# SCH.net
KiCad netlist of a schematic drawn in Altium Designer
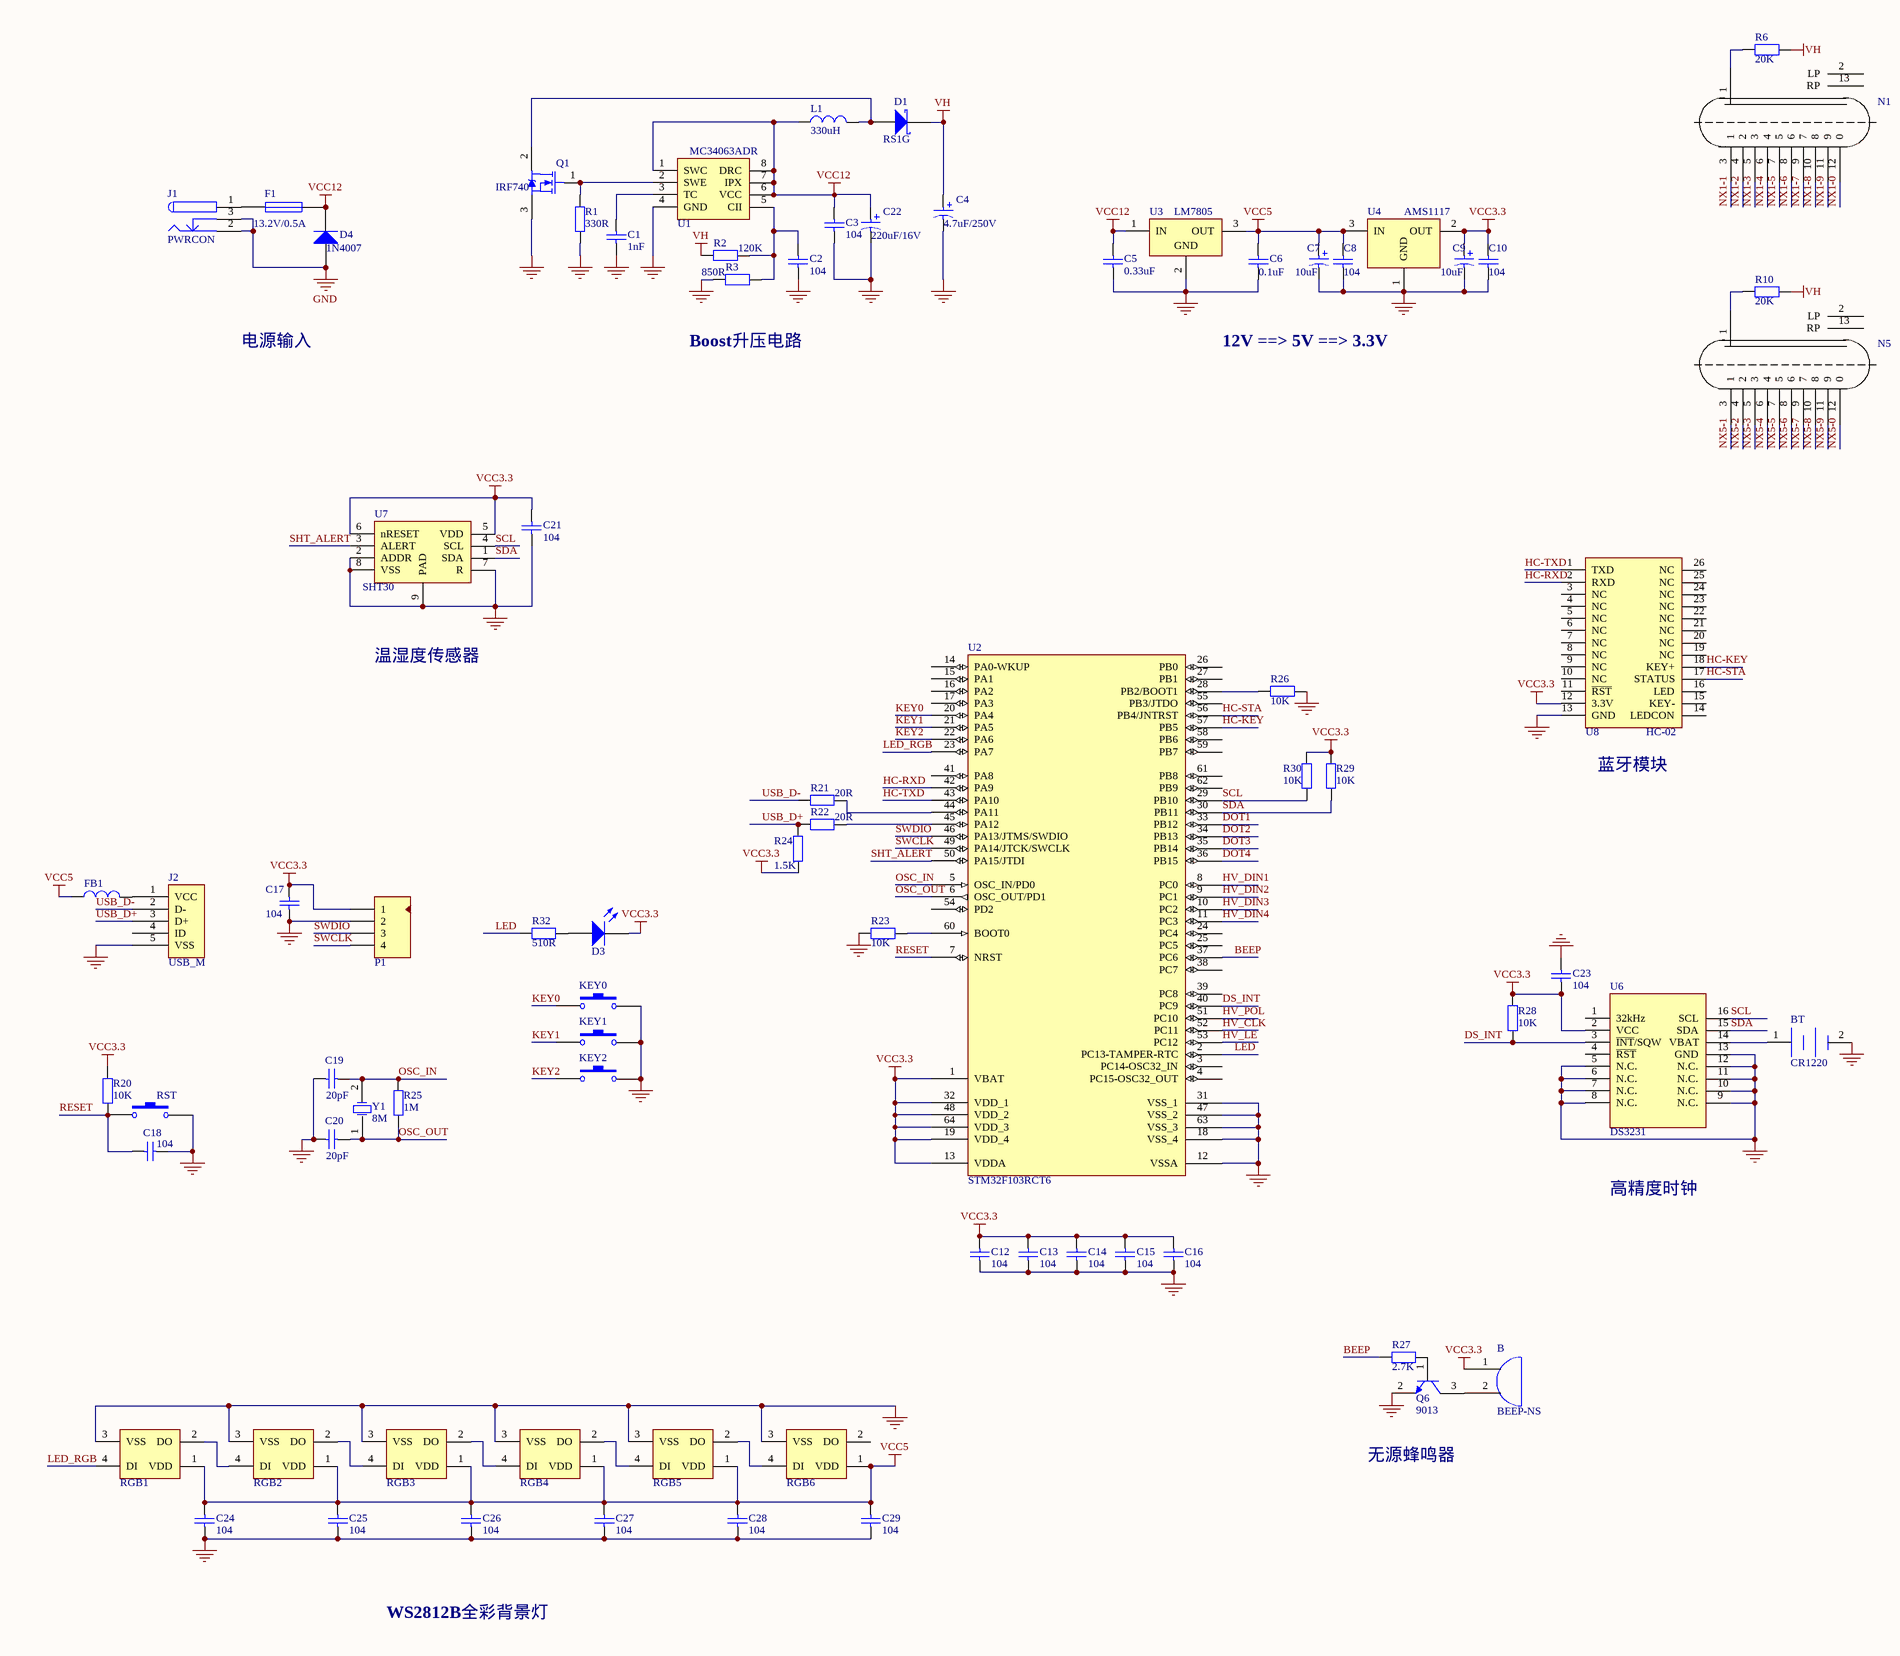
[diagram p0: SCH.SchDoc, left]
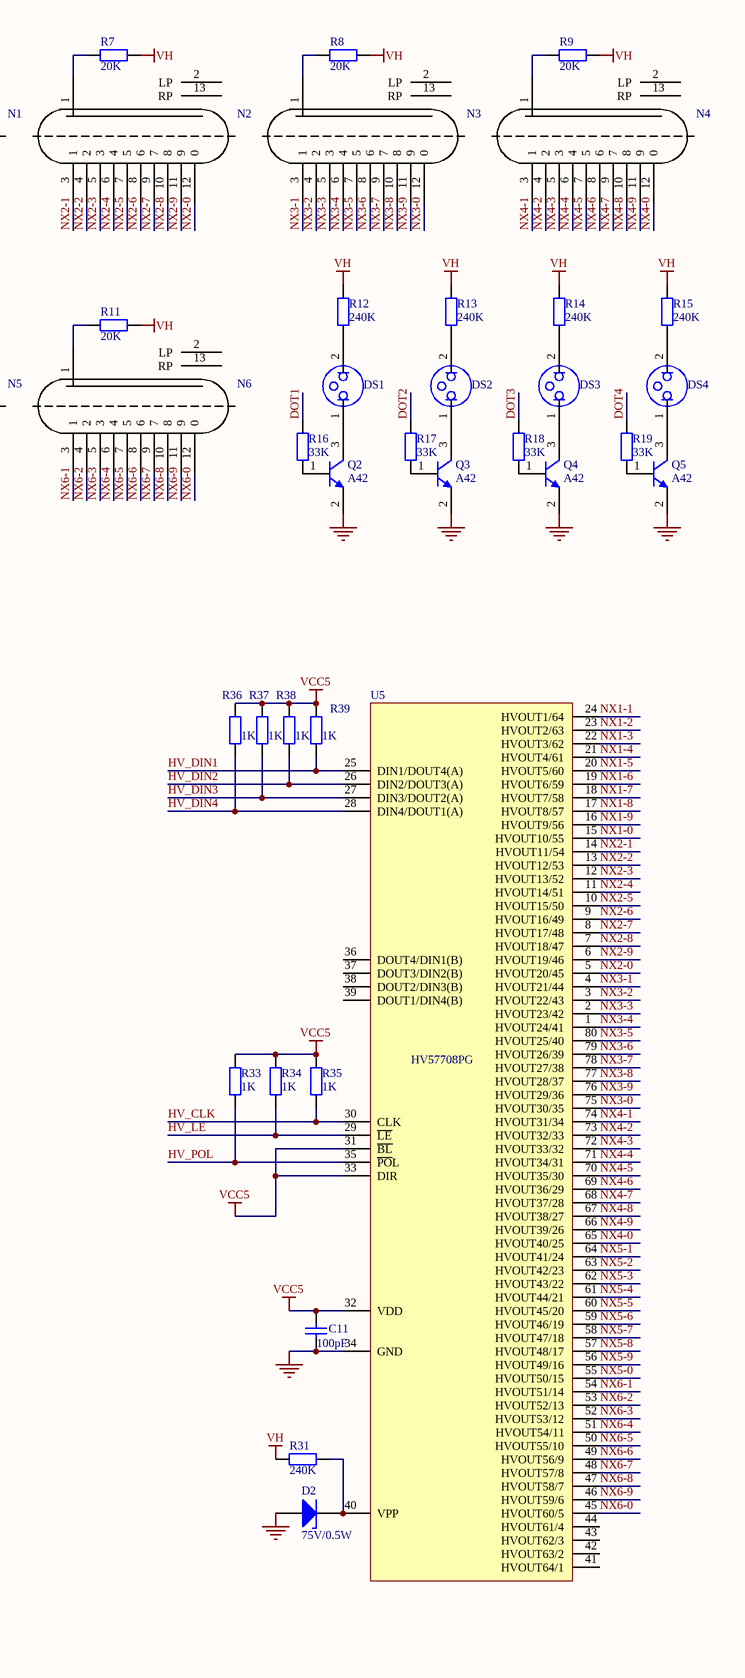
[diagram p1: SCH.SchDoc, right]

(export (version "E")
  (design (tool "Eeschema 10.0.6"))
  (components
    (comp (ref "B")
      (value "BEEP-NS")
      (footprint "BEEP-NS")
      (description "无源蜂鸣器")
      (libsource (lib "ChunLee") (part "BEEP-NS"))
    )
    (comp (ref "BT")
      (value "Battery")
      (footprint "CR1220")
      (fields (field (name "TYPE") "CR1220"))
      (libsource (lib "ChunLee") (part "Battery"))
    )
    (comp (ref "C1")
      (value "1nF")
      (footprint "C-0805")
      (description "贴片瓷片电容")
      (fields (field (name "Comment") "Cap-S") (field (name "PUBLISHER") "Altium Limited"))
      (libsource (lib "ChunLee") (part "Cap-S"))
    )
    (comp (ref "C2")
      (value "104")
      (footprint "C-0805")
      (description "贴片瓷片电容")
      (fields (field (name "Comment") "Cap-S") (field (name "PUBLISHER") "Altium Limited"))
      (libsource (lib "ChunLee") (part "Cap-S"))
    )
    (comp (ref "C3")
      (value "104")
      (footprint "C-0805")
      (description "贴片瓷片电容")
      (fields (field (name "Comment") "Cap-S") (field (name "PUBLISHER") "Altium Limited"))
      (libsource (lib "ChunLee") (part "Cap-S"))
    )
    (comp (ref "C4")
      (value "4.7uF/250V")
      (footprint "C-1812")
      (description "钽电容")
      (fields (field (name "Comment") "Cap-Pol") (field (name "PUBLISHER") "Altium Limited"))
      (libsource (lib "ChunLee") (part "Cap-Pol-A"))
    )
    (comp (ref "C5")
      (value "0.33uF")
      (footprint "C-1210")
      (description "贴片瓷片电容")
      (fields (field (name "Comment") "Cap-S") (field (name "PUBLISHER") "Altium Limited"))
      (libsource (lib "ChunLee") (part "Cap-S"))
    )
    (comp (ref "C6")
      (value "0.1uF")
      (footprint "C-1210")
      (description "贴片瓷片电容")
      (fields (field (name "Comment") "Cap-S") (field (name "PUBLISHER") "Altium Limited"))
      (libsource (lib "ChunLee") (part "Cap-S"))
    )
    (comp (ref "C7")
      (value "10uF")
      (footprint "C-1210")
      (description "钽电容")
      (fields (field (name "Comment") "Cap-Pol") (field (name "PUBLISHER") "Altium Limited"))
      (libsource (lib "ChunLee") (part "Cap-Pol-A"))
    )
    (comp (ref "C8")
      (value "104")
      (footprint "C-0805")
      (description "贴片瓷片电容")
      (fields (field (name "Comment") "Cap-S") (field (name "PUBLISHER") "Altium Limited"))
      (libsource (lib "ChunLee") (part "Cap-S"))
    )
    (comp (ref "C9")
      (value "10uF")
      (footprint "C-1210")
      (description "钽电容")
      (fields (field (name "Comment") "Cap-Pol") (field (name "PUBLISHER") "Altium Limited"))
      (libsource (lib "ChunLee") (part "Cap-Pol-A"))
    )
    (comp (ref "C10")
      (value "104")
      (footprint "C-0805")
      (description "贴片瓷片电容")
      (fields (field (name "Comment") "Cap-S") (field (name "PUBLISHER") "Altium Limited"))
      (libsource (lib "ChunLee") (part "Cap-S"))
    )
    (comp (ref "C11")
      (value "100pF")
      (footprint "C-0805")
      (description "贴片瓷片电容")
      (fields (field (name "Comment") "Cap-S") (field (name "PUBLISHER") "Altium Limited"))
      (libsource (lib "ChunLee") (part "Cap-S"))
    )
    (comp (ref "C12")
      (value "104")
      (footprint "C-0805")
      (description "贴片瓷片电容")
      (fields (field (name "Comment") "Cap-S") (field (name "PUBLISHER") "Altium Limited"))
      (libsource (lib "ChunLee") (part "Cap-S"))
    )
    (comp (ref "C13")
      (value "104")
      (footprint "C-0805")
      (description "贴片瓷片电容")
      (fields (field (name "Comment") "Cap-S") (field (name "PUBLISHER") "Altium Limited"))
      (libsource (lib "ChunLee") (part "Cap-S"))
    )
    (comp (ref "C14")
      (value "104")
      (footprint "C-0805")
      (description "贴片瓷片电容")
      (fields (field (name "Comment") "Cap-S") (field (name "PUBLISHER") "Altium Limited"))
      (libsource (lib "ChunLee") (part "Cap-S"))
    )
    (comp (ref "C15")
      (value "104")
      (footprint "C-0805")
      (description "贴片瓷片电容")
      (fields (field (name "Comment") "Cap-S") (field (name "PUBLISHER") "Altium Limited"))
      (libsource (lib "ChunLee") (part "Cap-S"))
    )
    (comp (ref "C16")
      (value "104")
      (footprint "C-0805")
      (description "贴片瓷片电容")
      (fields (field (name "Comment") "Cap-S") (field (name "PUBLISHER") "Altium Limited"))
      (libsource (lib "ChunLee") (part "Cap-S"))
    )
    (comp (ref "C17")
      (value "104")
      (footprint "C-0805")
      (description "贴片瓷片电容")
      (fields (field (name "Comment") "Cap-S") (field (name "PUBLISHER") "Altium Limited"))
      (libsource (lib "ChunLee") (part "Cap-S"))
    )
    (comp (ref "C18")
      (value "104")
      (footprint "C-0805")
      (description "贴片瓷片电容")
      (fields (field (name "Comment") "Cap-S") (field (name "PUBLISHER") "Altium Limited"))
      (libsource (lib "ChunLee") (part "Cap-S"))
    )
    (comp (ref "C19")
      (value "20pF")
      (footprint "C-0805")
      (description "贴片瓷片电容")
      (fields (field (name "Comment") "Cap-S") (field (name "PUBLISHER") "Altium Limited"))
      (libsource (lib "ChunLee") (part "Cap-S"))
    )
    (comp (ref "C20")
      (value "20pF")
      (footprint "C-0805")
      (description "贴片瓷片电容")
      (fields (field (name "Comment") "Cap-S") (field (name "PUBLISHER") "Altium Limited"))
      (libsource (lib "ChunLee") (part "Cap-S"))
    )
    (comp (ref "C21")
      (value "104")
      (footprint "C-0805")
      (description "贴片瓷片电容")
      (fields (field (name "Comment") "Cap-S") (field (name "PUBLISHER") "Altium Limited"))
      (libsource (lib "ChunLee") (part "Cap-S"))
    )
    (comp (ref "C22")
      (value "220uF/16V")
      (footprint "C-RB-SMD6.3x7.7")
      (description "贴片铝电解电容")
      (fields (field (name "Comment") "Cap-Pol-ES") (field (name "PUBLISHER") "Altium Limited"))
      (libsource (lib "ChunLee") (part "Cap-Pol-ES"))
    )
    (comp (ref "C23")
      (value "104")
      (footprint "C-0805")
      (description "贴片瓷片电容")
      (fields (field (name "Comment") "Cap-S") (field (name "PUBLISHER") "Altium Limited"))
      (libsource (lib "ChunLee") (part "Cap-S"))
    )
    (comp (ref "C24")
      (value "104")
      (footprint "C-0805")
      (description "贴片瓷片电容")
      (fields (field (name "Comment") "Cap-S") (field (name "PUBLISHER") "Altium Limited"))
      (libsource (lib "ChunLee") (part "Cap-S"))
    )
    (comp (ref "C25")
      (value "104")
      (footprint "C-0805")
      (description "贴片瓷片电容")
      (fields (field (name "Comment") "Cap-S") (field (name "PUBLISHER") "Altium Limited"))
      (libsource (lib "ChunLee") (part "Cap-S"))
    )
    (comp (ref "C26")
      (value "104")
      (footprint "C-0805")
      (description "贴片瓷片电容")
      (fields (field (name "Comment") "Cap-S") (field (name "PUBLISHER") "Altium Limited"))
      (libsource (lib "ChunLee") (part "Cap-S"))
    )
    (comp (ref "C27")
      (value "104")
      (footprint "C-0805")
      (description "贴片瓷片电容")
      (fields (field (name "Comment") "Cap-S") (field (name "PUBLISHER") "Altium Limited"))
      (libsource (lib "ChunLee") (part "Cap-S"))
    )
    (comp (ref "C28")
      (value "104")
      (footprint "C-0805")
      (description "贴片瓷片电容")
      (fields (field (name "Comment") "Cap-S") (field (name "PUBLISHER") "Altium Limited"))
      (libsource (lib "ChunLee") (part "Cap-S"))
    )
    (comp (ref "C29")
      (value "104")
      (footprint "C-0805")
      (description "贴片瓷片电容")
      (fields (field (name "Comment") "Cap-S") (field (name "PUBLISHER") "Altium Limited"))
      (libsource (lib "ChunLee") (part "Cap-S"))
    )
    (comp (ref "D1")
      (value "RS1G")
      (footprint "D-SMA")
      (description "快恢复二极管")
      (fields (field (name "PUBLISHER") "Altium Limited"))
      (libsource (lib "ChunLee") (part "Diode-Schottky"))
    )
    (comp (ref "D2")
      (value "75V/0.5W")
      (footprint "D-ll34")
      (description "稳压二极管")
      (fields (field (name "Comment") "ZMM75") (field (name "PUBLISHER") "Altium Limited"))
      (libsource (lib "ChunLee") (part "Diode-Z"))
    )
    (comp (ref "D3")
      (value "LED0")
      (footprint "LED-0805")
      (description "发光二极管")
      (fields (field (name "PUBLISHER") "Altium Limited"))
      (libsource (lib "ChunLee") (part "LED0"))
    )
    (comp (ref "D4")
      (value "1N4007")
      (footprint "D-SMA")
      (description "整流二极管")
      (fields (field (name "PUBLISHER") "Altium Limited"))
      (libsource (lib "ChunLee") (part "Diode"))
    )
    (comp (ref "DS1")
      (value "Neon")
      (footprint "PIN2")
      (description "氖泡")
      (libsource (lib "ChunLee") (part "Neon_Lamp"))
    )
    (comp (ref "DS2")
      (value "Neon")
      (footprint "PIN2")
      (description "氖泡")
      (libsource (lib "ChunLee") (part "Neon_Lamp"))
    )
    (comp (ref "DS3")
      (value "Neon")
      (footprint "PIN2")
      (description "氖泡")
      (libsource (lib "ChunLee") (part "Neon_Lamp"))
    )
    (comp (ref "DS4")
      (value "Neon")
      (footprint "PIN2")
      (description "氖泡")
      (libsource (lib "ChunLee") (part "Neon_Lamp"))
    )
    (comp (ref "F1")
      (value "13.2V/0.5A")
      (footprint "1206")
      (description "保险丝")
      (fields (field (name "Comment") "Fuse1"))
      (libsource (lib "ChunLee") (part "Fuse1"))
    )
    (comp (ref "FB1")
      (value "Inductor")
      (footprint "0805-1")
      (description "磁珠")
      (fields (field (name "PUBLISHER") "Altium Limited"))
      (libsource (lib "ChunLee") (part "Inductor"))
    )
    (comp (ref "J1")
      (value "PWRCON")
      (footprint "DC-005")
      (description "直流电源端子")
      (fields (field (name "PUBLISHER") "Altium Limited"))
      (libsource (lib "HDR_ChunLee") (part "PWRCON"))
    )
    (comp (ref "J2")
      (value "USB_M")
      (footprint "USB_MICRO")
      (description "Micro/Mini USB")
      (libsource (lib "HDR_ChunLee") (part "USB_M"))
    )
    (comp (ref "KEY0")
      (value "KEY")
      (footprint "SW_PB2_C1")
      (description "微动开关")
      (fields (field (name "PUBLISHER") "Altium Limited"))
      (libsource (lib "ChunLee") (part "SW-PB"))
    )
    (comp (ref "KEY1")
      (value "KEY")
      (footprint "SW_PB2_C1")
      (description "微动开关")
      (fields (field (name "PUBLISHER") "Altium Limited"))
      (libsource (lib "ChunLee") (part "SW-PB"))
    )
    (comp (ref "KEY2")
      (value "KEY")
      (footprint "SW_PB2_C1")
      (description "微动开关")
      (fields (field (name "PUBLISHER") "Altium Limited"))
      (libsource (lib "ChunLee") (part "SW-PB"))
    )
    (comp (ref "L1")
      (value "330uH")
      (footprint "L-SMD-12")
      (description "电感")
      (fields (field (name "Comment") "Inductor") (field (name "PUBLISHER") "Altium Limited"))
      (libsource (lib "ChunLee") (part "Inductor"))
    )
    (comp (ref "N1")
      (value "IN_14")
      (footprint "IN_14")
      (description "辉光管")
      (libsource (lib "ChunLee") (part "IN_14"))
    )
    (comp (ref "N2")
      (value "IN_14")
      (footprint "IN_14")
      (description "辉光管")
      (libsource (lib "ChunLee") (part "IN_14"))
    )
    (comp (ref "N3")
      (value "IN_14")
      (footprint "IN_14")
      (description "辉光管")
      (libsource (lib "ChunLee") (part "IN_14"))
    )
    (comp (ref "N4")
      (value "IN_14")
      (footprint "IN_14")
      (description "辉光管")
      (libsource (lib "ChunLee") (part "IN_14"))
    )
    (comp (ref "N5")
      (value "IN_14")
      (footprint "IN_14")
      (description "辉光管")
      (libsource (lib "ChunLee") (part "IN_14"))
    )
    (comp (ref "N6")
      (value "IN_14")
      (footprint "IN_14")
      (description "辉光管")
      (libsource (lib "ChunLee") (part "IN_14"))
    )
    (comp (ref "P1")
      (value "Header 4")
      (footprint "HDR4X1-2.54")
      (description "接插件")
      (fields (field (name "PUBLISHER") "Altium Limited"))
      (libsource (lib "HDR_ChunLee") (part "Header 4"))
    )
    (comp (ref "Q1")
      (value "IRF740")
      (footprint "TO263-2")
      (description "N-Channel MOSFET")
      (fields (field (name "PUBLISHER") "Altium Limited"))
      (libsource (lib "ChunLee") (part "MOSFET-N"))
    )
    (comp (ref "Q2")
      (value "A42")
      (footprint "SOT23-3")
      (description "贴片三极管")
      (fields (field (name "PUBLISHER") "Altium Limited"))
      (libsource (lib "ChunLee") (part "NPN1"))
    )
    (comp (ref "Q3")
      (value "A42")
      (footprint "SOT23-3")
      (description "贴片三极管")
      (fields (field (name "PUBLISHER") "Altium Limited"))
      (libsource (lib "ChunLee") (part "NPN1"))
    )
    (comp (ref "Q4")
      (value "A42")
      (footprint "SOT23-3")
      (description "贴片三极管")
      (fields (field (name "PUBLISHER") "Altium Limited"))
      (libsource (lib "ChunLee") (part "NPN1"))
    )
    (comp (ref "Q5")
      (value "A42")
      (footprint "SOT23-3")
      (description "贴片三极管")
      (fields (field (name "PUBLISHER") "Altium Limited"))
      (libsource (lib "ChunLee") (part "NPN1"))
    )
    (comp (ref "Q6")
      (value "9013")
      (footprint "SOT23-3")
      (description "贴片三极管")
      (fields (field (name "PUBLISHER") "Altium Limited"))
      (libsource (lib "ChunLee") (part "NPN1"))
    )
    (comp (ref "R1")
      (value "330R")
      (footprint "0805-1")
      (description "贴片电阻")
      (fields (field (name "Comment") "Res1") (field (name "PUBLISHER") "Altium Limited"))
      (libsource (lib "") (part "Res1_1"))
    )
    (comp (ref "R2")
      (value "120K")
      (footprint "0805-1")
      (description "贴片电阻")
      (fields (field (name "Comment") "Res1") (field (name "PUBLISHER") "Altium Limited"))
      (libsource (lib "") (part "Res1_2"))
    )
    (comp (ref "R3")
      (value "850R")
      (footprint "0805-1")
      (description "贴片电阻")
      (fields (field (name "Comment") "Res1") (field (name "PUBLISHER") "Altium Limited"))
      (libsource (lib "") (part "Res1_2"))
    )
    (comp (ref "R6")
      (value "20K")
      (footprint "0805-1")
      (description "贴片电阻")
      (fields (field (name "Comment") "Res1") (field (name "PUBLISHER") "Altium Limited"))
      (libsource (lib "") (part "Res1_2"))
    )
    (comp (ref "R7")
      (value "20K")
      (footprint "0805-1")
      (description "贴片电阻")
      (fields (field (name "Comment") "Res1") (field (name "PUBLISHER") "Altium Limited"))
      (libsource (lib "") (part "Res1_2"))
    )
    (comp (ref "R8")
      (value "20K")
      (footprint "0805-1")
      (description "贴片电阻")
      (fields (field (name "Comment") "Res1") (field (name "PUBLISHER") "Altium Limited"))
      (libsource (lib "") (part "Res1_2"))
    )
    (comp (ref "R9")
      (value "20K")
      (footprint "0805-1")
      (description "贴片电阻")
      (fields (field (name "Comment") "Res1") (field (name "PUBLISHER") "Altium Limited"))
      (libsource (lib "") (part "Res1_2"))
    )
    (comp (ref "R10")
      (value "20K")
      (footprint "0805-1")
      (description "贴片电阻")
      (fields (field (name "Comment") "Res1") (field (name "PUBLISHER") "Altium Limited"))
      (libsource (lib "") (part "Res1_2"))
    )
    (comp (ref "R11")
      (value "20K")
      (footprint "0805-1")
      (description "贴片电阻")
      (fields (field (name "Comment") "Res1") (field (name "PUBLISHER") "Altium Limited"))
      (libsource (lib "") (part "Res1_2"))
    )
    (comp (ref "R12")
      (value "240K")
      (footprint "0805-1")
      (description "贴片电阻")
      (fields (field (name "Comment") "Res1") (field (name "PUBLISHER") "Altium Limited"))
      (libsource (lib "ChunLee") (part "Res1"))
    )
    (comp (ref "R13")
      (value "240K")
      (footprint "0805-1")
      (description "贴片电阻")
      (fields (field (name "Comment") "Res1") (field (name "PUBLISHER") "Altium Limited"))
      (libsource (lib "ChunLee") (part "Res1"))
    )
    (comp (ref "R14")
      (value "240K")
      (footprint "0805-1")
      (description "贴片电阻")
      (fields (field (name "Comment") "Res1") (field (name "PUBLISHER") "Altium Limited"))
      (libsource (lib "") (part "Res1_1"))
    )
    (comp (ref "R15")
      (value "240K")
      (footprint "0805-1")
      (description "贴片电阻")
      (fields (field (name "Comment") "Res1") (field (name "PUBLISHER") "Altium Limited"))
      (libsource (lib "ChunLee") (part "Res1"))
    )
    (comp (ref "R16")
      (value "33K")
      (footprint "0805-1")
      (description "贴片电阻")
      (fields (field (name "Comment") "Res1") (field (name "PUBLISHER") "Altium Limited"))
      (libsource (lib "ChunLee") (part "Res1"))
    )
    (comp (ref "R17")
      (value "33K")
      (footprint "0805-1")
      (description "贴片电阻")
      (fields (field (name "Comment") "Res1") (field (name "PUBLISHER") "Altium Limited"))
      (libsource (lib "ChunLee") (part "Res1"))
    )
    (comp (ref "R18")
      (value "33K")
      (footprint "0805-1")
      (description "贴片电阻")
      (fields (field (name "Comment") "Res1") (field (name "PUBLISHER") "Altium Limited"))
      (libsource (lib "ChunLee") (part "Res1"))
    )
    (comp (ref "R19")
      (value "33K")
      (footprint "0805-1")
      (description "贴片电阻")
      (fields (field (name "Comment") "Res1") (field (name "PUBLISHER") "Altium Limited"))
      (libsource (lib "ChunLee") (part "Res1"))
    )
    (comp (ref "R20")
      (value "10K")
      (footprint "0805-1")
      (description "贴片电阻")
      (fields (field (name "Comment") "Res1") (field (name "PUBLISHER") "Altium Limited"))
      (libsource (lib "") (part "Res1_1"))
    )
    (comp (ref "R21")
      (value "20R")
      (footprint "0805-1")
      (description "贴片电阻")
      (fields (field (name "Comment") "Res1") (field (name "PUBLISHER") "Altium Limited"))
      (libsource (lib "") (part "Res1_2"))
    )
    (comp (ref "R22")
      (value "20R")
      (footprint "0805-1")
      (description "贴片电阻")
      (fields (field (name "Comment") "Res1") (field (name "PUBLISHER") "Altium Limited"))
      (libsource (lib "") (part "Res1_2"))
    )
    (comp (ref "R23")
      (value "10K")
      (footprint "0805-1")
      (description "贴片电阻")
      (fields (field (name "Comment") "Res1") (field (name "PUBLISHER") "Altium Limited"))
      (libsource (lib "") (part "Res1_2"))
    )
    (comp (ref "R24")
      (value "1.5K")
      (footprint "0805-1")
      (description "贴片电阻")
      (fields (field (name "Comment") "Res1") (field (name "PUBLISHER") "Altium Limited"))
      (libsource (lib "ChunLee") (part "Res1"))
    )
    (comp (ref "R25")
      (value "1M")
      (footprint "0805-1")
      (description "贴片电阻")
      (fields (field (name "Comment") "Res1") (field (name "PUBLISHER") "Altium Limited"))
      (libsource (lib "") (part "Res1_1"))
    )
    (comp (ref "R26")
      (value "10K")
      (footprint "0805-1")
      (description "贴片电阻")
      (fields (field (name "Comment") "Res1") (field (name "PUBLISHER") "Altium Limited"))
      (libsource (lib "") (part "Res1_2"))
    )
    (comp (ref "R27")
      (value "2.7K")
      (footprint "0805-1")
      (description "贴片电阻")
      (fields (field (name "Comment") "Res1") (field (name "PUBLISHER") "Altium Limited"))
      (libsource (lib "") (part "Res1_2"))
    )
    (comp (ref "R28")
      (value "10K")
      (footprint "0805-1")
      (description "贴片电阻")
      (fields (field (name "Comment") "Res1") (field (name "PUBLISHER") "Altium Limited"))
      (libsource (lib "") (part "Res1_1"))
    )
    (comp (ref "R29")
      (value "10K")
      (footprint "0805-1")
      (description "贴片电阻")
      (fields (field (name "Comment") "Res1") (field (name "PUBLISHER") "Altium Limited"))
      (libsource (lib "") (part "Res1_1"))
    )
    (comp (ref "R30")
      (value "10K")
      (footprint "0805-1")
      (description "贴片电阻")
      (fields (field (name "Comment") "Res1") (field (name "PUBLISHER") "Altium Limited"))
      (libsource (lib "") (part "Res1_1"))
    )
    (comp (ref "R31")
      (value "240K")
      (footprint "1206")
      (description "贴片电阻")
      (fields (field (name "Comment") "Res1") (field (name "PUBLISHER") "Altium Limited"))
      (libsource (lib "") (part "Res1_2"))
    )
    (comp (ref "R32")
      (value "510R")
      (footprint "0805-1")
      (description "贴片电阻")
      (fields (field (name "Comment") "Res1") (field (name "PUBLISHER") "Altium Limited"))
      (libsource (lib "") (part "Res1_2"))
    )
    (comp (ref "R33")
      (value "1K")
      (footprint "0805-1")
      (description "贴片电阻")
      (fields (field (name "Comment") "Res1") (field (name "PUBLISHER") "Altium Limited"))
      (libsource (lib "") (part "Res1_1"))
    )
    (comp (ref "R34")
      (value "1K")
      (footprint "0805-1")
      (description "贴片电阻")
      (fields (field (name "Comment") "Res1") (field (name "PUBLISHER") "Altium Limited"))
      (libsource (lib "") (part "Res1_1"))
    )
    (comp (ref "R35")
      (value "1K")
      (footprint "0805-1")
      (description "贴片电阻")
      (fields (field (name "Comment") "Res1") (field (name "PUBLISHER") "Altium Limited"))
      (libsource (lib "") (part "Res1_1"))
    )
    (comp (ref "R36")
      (value "1K")
      (footprint "0805-1")
      (description "贴片电阻")
      (fields (field (name "Comment") "Res1") (field (name "PUBLISHER") "Altium Limited"))
      (libsource (lib "") (part "Res1_1"))
    )
    (comp (ref "R37")
      (value "1K")
      (footprint "0805-1")
      (description "贴片电阻")
      (fields (field (name "Comment") "Res1") (field (name "PUBLISHER") "Altium Limited"))
      (libsource (lib "") (part "Res1_1"))
    )
    (comp (ref "R38")
      (value "1K")
      (footprint "0805-1")
      (description "贴片电阻")
      (fields (field (name "Comment") "Res1") (field (name "PUBLISHER") "Altium Limited"))
      (libsource (lib "") (part "Res1_1"))
    )
    (comp (ref "R39")
      (value "1K")
      (footprint "0805-1")
      (description "贴片电阻")
      (fields (field (name "Comment") "Res1") (field (name "PUBLISHER") "Altium Limited"))
      (libsource (lib "") (part "Res1_1"))
    )
    (comp (ref "RGB1")
      (value "WS2812B")
      (footprint "SMD-5050-4")
      (description "WS2812B 4脚RGB全彩LED")
      (libsource (lib "ChunLee") (part "WS2812B"))
    )
    (comp (ref "RGB2")
      (value "WS2812B")
      (footprint "SMD-5050-4")
      (description "WS2812B 4脚RGB全彩LED")
      (libsource (lib "ChunLee") (part "WS2812B"))
    )
    (comp (ref "RGB3")
      (value "WS2812B")
      (footprint "SMD-5050-4")
      (description "WS2812B 4脚RGB全彩LED")
      (libsource (lib "ChunLee") (part "WS2812B"))
    )
    (comp (ref "RGB4")
      (value "WS2812B")
      (footprint "SMD-5050-4")
      (description "WS2812B 4脚RGB全彩LED")
      (libsource (lib "ChunLee") (part "WS2812B"))
    )
    (comp (ref "RGB5")
      (value "WS2812B")
      (footprint "SMD-5050-4")
      (description "WS2812B 4脚RGB全彩LED")
      (libsource (lib "ChunLee") (part "WS2812B"))
    )
    (comp (ref "RGB6")
      (value "WS2812B")
      (footprint "SMD-5050-4")
      (description "WS2812B 4脚RGB全彩LED")
      (libsource (lib "ChunLee") (part "WS2812B"))
    )
    (comp (ref "RST")
      (value "SW-PB")
      (footprint "SW_PB2_A1")
      (description "微动开关")
      (fields (field (name "PUBLISHER") "Altium Limited"))
      (libsource (lib "ChunLee") (part "SW-PB"))
    )
    (comp (ref "U1")
      (value "MC34063ADR")
      (footprint "SOIC-8P")
      (description "开关变压器芯片")
      (libsource (lib "ChunLee") (part "MC34063ADR"))
    )
    (comp (ref "U2")
      (value "STM32F103RCT6")
      (footprint "LQFP-64")
      (description "STM32F103, 64引脚, 256Kb Flash, 48Kb SRAM")
      (fields (field (name "PUBLISHER") "Altium Limited"))
      (libsource (lib "ChunLee") (part "STM32F103RCT6"))
    )
    (comp (ref "U3")
      (value "LM7805")
      (footprint "DPAK")
      (description "Series 3-Terminal Positive Regulator")
      (libsource (lib "ChunLee") (part "LM7805CT"))
    )
    (comp (ref "U4")
      (value "AMS1117")
      (footprint "SOT223")
      (description "3.3V稳压芯片")
      (libsource (lib "ChunLee") (part "AMS1117"))
    )
    (comp (ref "U5")
      (value "HV57708PG")
      (footprint "PQFP-80")
      (description "32MHz, 64通道推挽输出串入并出芯片")
      (libsource (lib "ChunLee") (part "HV57708PG"))
    )
    (comp (ref "U6")
      (value "DS3231")
      (footprint "SOIC-16W")
      (description "高精度时钟芯片")
      (libsource (lib "ChunLee") (part "DS3231"))
    )
    (comp (ref "U7")
      (value "SHT30")
      (footprint "SHT3x-DIS")
      (description "温湿度传感器")
      (libsource (lib "ChunLee") (part "SHT3X"))
    )
    (comp (ref "U8")
      (value "HC-02")
      (footprint "HC-02")
      (description "串口蓝牙4.0, 10m")
      (libsource (lib "ChunLee") (part "HC-02"))
    )
    (comp (ref "Y1")
      (value "8M")
      (footprint "X-SM49")
      (description "晶振")
      (fields (field (name "Comment") "XTAL") (field (name "PUBLISHER") "Altium Limited"))
      (libsource (lib "ChunLee") (part "XTAL"))
    )
  )
  (nets
    (net (code "1") (name "/BEEP") (class "Default")
      (node (ref "R27") (pin "1") (pinfunction "1_1") (pintype "passive"))
      (node (ref "U2") (pin "37") (pinfunction "PC6_37") (pintype "bidirectional"))
    )
    (net (code "2") (name "/DOT1") (class "Default")
      (node (ref "R16") (pin "1") (pinfunction "1_1") (pintype "passive"))
      (node (ref "U2") (pin "33") (pinfunction "PB12_33") (pintype "bidirectional"))
    )
    (net (code "3") (name "/DOT2") (class "Default")
      (node (ref "R17") (pin "1") (pinfunction "1_1") (pintype "passive"))
      (node (ref "U2") (pin "34") (pinfunction "PB13_34") (pintype "bidirectional"))
    )
    (net (code "4") (name "/DOT3") (class "Default")
      (node (ref "R18") (pin "1") (pinfunction "1_1") (pintype "passive"))
      (node (ref "U2") (pin "35") (pinfunction "PB14_35") (pintype "bidirectional"))
    )
    (net (code "5") (name "/DOT4") (class "Default")
      (node (ref "R19") (pin "1") (pinfunction "1_1") (pintype "passive"))
      (node (ref "U2") (pin "36") (pinfunction "PB15_36") (pintype "bidirectional"))
    )
    (net (code "6") (name "/DS_INT") (class "Default")
      (node (ref "R28") (pin "1") (pinfunction "1_1") (pintype "passive"))
      (node (ref "U2") (pin "40") (pinfunction "PC9_40") (pintype "bidirectional"))
      (node (ref "U6") (pin "3") (pinfunction "~{INT}/SQW_3") (pintype "passive"))
    )
    (net (code "7") (name "/HC-KEY") (class "Default")
      (node (ref "U2") (pin "57") (pinfunction "PB5_57") (pintype "bidirectional"))
      (node (ref "U8") (pin "18") (pinfunction "KEY+_18") (pintype "passive"))
    )
    (net (code "8") (name "/HC-RXD") (class "Default")
      (node (ref "U2") (pin "42") (pinfunction "PA9_42") (pintype "bidirectional"))
      (node (ref "U8") (pin "2") (pinfunction "RXD_2") (pintype "passive"))
    )
    (net (code "9") (name "/HC-STA") (class "Default")
      (node (ref "U2") (pin "56") (pinfunction "PB4/JNTRST_56") (pintype "bidirectional"))
      (node (ref "U8") (pin "17") (pinfunction "STATUS_17") (pintype "passive"))
    )
    (net (code "10") (name "/HC-TXD") (class "Default")
      (node (ref "U2") (pin "43") (pinfunction "PA10_43") (pintype "bidirectional"))
      (node (ref "U8") (pin "1") (pinfunction "TXD_1") (pintype "passive"))
    )
    (net (code "11") (name "/HV_CLK") (class "Default")
      (node (ref "R35") (pin "1") (pinfunction "1_1") (pintype "passive"))
      (node (ref "U2") (pin "52") (pinfunction "PC11_52") (pintype "bidirectional"))
      (node (ref "U5") (pin "30") (pinfunction "CLK_30") (pintype "passive"))
    )
    (net (code "12") (name "/HV_DIN1") (class "Default")
      (node (ref "R39") (pin "1") (pinfunction "1_1") (pintype "passive"))
      (node (ref "U2") (pin "8") (pinfunction "PC0_8") (pintype "bidirectional"))
      (node (ref "U5") (pin "25") (pinfunction "DIN1/DOUT4(A)_25") (pintype "passive"))
    )
    (net (code "13") (name "/HV_DIN2") (class "Default")
      (node (ref "R38") (pin "1") (pinfunction "1_1") (pintype "passive"))
      (node (ref "U2") (pin "9") (pinfunction "PC1_9") (pintype "bidirectional"))
      (node (ref "U5") (pin "26") (pinfunction "DIN2/DOUT3(A)_26") (pintype "passive"))
    )
    (net (code "14") (name "/HV_DIN3") (class "Default")
      (node (ref "R37") (pin "1") (pinfunction "1_1") (pintype "passive"))
      (node (ref "U2") (pin "10") (pinfunction "PC2_10") (pintype "bidirectional"))
      (node (ref "U5") (pin "27") (pinfunction "DIN3/DOUT2(A)_27") (pintype "passive"))
    )
    (net (code "15") (name "/HV_DIN4") (class "Default")
      (node (ref "R36") (pin "1") (pinfunction "1_1") (pintype "passive"))
      (node (ref "U2") (pin "11") (pinfunction "PC3_11") (pintype "bidirectional"))
      (node (ref "U5") (pin "28") (pinfunction "DIN4/DOUT1(A)_28") (pintype "passive"))
    )
    (net (code "16") (name "/HV_LE") (class "Default")
      (node (ref "R34") (pin "1") (pinfunction "1_1") (pintype "passive"))
      (node (ref "U2") (pin "53") (pinfunction "PC12_53") (pintype "bidirectional"))
      (node (ref "U5") (pin "29") (pinfunction "~{LE}_29") (pintype "passive"))
    )
    (net (code "17") (name "/HV_POL") (class "Default")
      (node (ref "R33") (pin "1") (pinfunction "1_1") (pintype "passive"))
      (node (ref "U2") (pin "51") (pinfunction "PC10_51") (pintype "bidirectional"))
      (node (ref "U5") (pin "35") (pinfunction "~{PO}L_35") (pintype "passive"))
    )
    (net (code "18") (name "/KEY0") (class "Default")
      (node (ref "KEY0") (pin "1") (pinfunction "1_1") (pintype "passive"))
      (node (ref "U2") (pin "20") (pinfunction "PA4_20") (pintype "bidirectional"))
    )
    (net (code "19") (name "/KEY1") (class "Default")
      (node (ref "KEY1") (pin "1") (pinfunction "1_1") (pintype "passive"))
      (node (ref "U2") (pin "21") (pinfunction "PA5_21") (pintype "bidirectional"))
    )
    (net (code "20") (name "/KEY2") (class "Default")
      (node (ref "KEY2") (pin "1") (pinfunction "1_1") (pintype "passive"))
      (node (ref "U2") (pin "22") (pinfunction "PA6_22") (pintype "bidirectional"))
    )
    (net (code "21") (name "/LED") (class "Default")
      (node (ref "R32") (pin "1") (pinfunction "1_1") (pintype "passive"))
      (node (ref "U2") (pin "2") (pinfunction "PC13-TAMPER-RTC_2") (pintype "bidirectional"))
    )
    (net (code "22") (name "/LED_RGB") (class "Default")
      (node (ref "RGB1") (pin "4") (pinfunction "DI_4") (pintype "passive"))
      (node (ref "U2") (pin "23") (pinfunction "PA7_23") (pintype "bidirectional"))
    )
    (net (code "23") (name "/NX1-0") (class "Default")
      (node (ref "N1") (pin "12") (pinfunction "0_12") (pintype "passive"))
      (node (ref "U5") (pin "15") (pinfunction "HVOUT10/55_15") (pintype "passive"))
    )
    (net (code "24") (name "/NX1-1") (class "Default")
      (node (ref "N1") (pin "3") (pinfunction "1_3") (pintype "passive"))
      (node (ref "U5") (pin "24") (pinfunction "HVOUT1/64_24") (pintype "passive"))
    )
    (net (code "25") (name "/NX1-2") (class "Default")
      (node (ref "N1") (pin "4") (pinfunction "2_4") (pintype "passive"))
      (node (ref "U5") (pin "23") (pinfunction "HVOUT2/63_23") (pintype "passive"))
    )
    (net (code "26") (name "/NX1-3") (class "Default")
      (node (ref "N1") (pin "5") (pinfunction "3_5") (pintype "passive"))
      (node (ref "U5") (pin "22") (pinfunction "HVOUT3/62_22") (pintype "passive"))
    )
    (net (code "27") (name "/NX1-4") (class "Default")
      (node (ref "N1") (pin "6") (pinfunction "4_6") (pintype "passive"))
      (node (ref "U5") (pin "21") (pinfunction "HVOUT4/61_21") (pintype "passive"))
    )
    (net (code "28") (name "/NX1-5") (class "Default")
      (node (ref "N1") (pin "7") (pinfunction "5_7") (pintype "passive"))
      (node (ref "U5") (pin "20") (pinfunction "HVOUT5/60_20") (pintype "passive"))
    )
    (net (code "29") (name "/NX1-6") (class "Default")
      (node (ref "N1") (pin "8") (pinfunction "6_8") (pintype "passive"))
      (node (ref "U5") (pin "19") (pinfunction "HVOUT6/59_19") (pintype "passive"))
    )
    (net (code "30") (name "/NX1-7") (class "Default")
      (node (ref "N1") (pin "9") (pinfunction "7_9") (pintype "passive"))
      (node (ref "U5") (pin "18") (pinfunction "HVOUT7/58_18") (pintype "passive"))
    )
    (net (code "31") (name "/NX1-8") (class "Default")
      (node (ref "N1") (pin "10") (pinfunction "8_10") (pintype "passive"))
      (node (ref "U5") (pin "17") (pinfunction "HVOUT8/57_17") (pintype "passive"))
    )
    (net (code "32") (name "/NX1-9") (class "Default")
      (node (ref "N1") (pin "11") (pinfunction "9_11") (pintype "passive"))
      (node (ref "U5") (pin "16") (pinfunction "HVOUT9/56_16") (pintype "passive"))
    )
    (net (code "33") (name "/NX2-0") (class "Default")
      (node (ref "N2") (pin "12") (pinfunction "0_12") (pintype "passive"))
      (node (ref "U5") (pin "5") (pinfunction "HVOUT20/45_5") (pintype "passive"))
    )
    (net (code "34") (name "/NX2-1") (class "Default")
      (node (ref "N2") (pin "3") (pinfunction "1_3") (pintype "passive"))
      (node (ref "U5") (pin "14") (pinfunction "HVOUT11/54_14") (pintype "passive"))
    )
    (net (code "35") (name "/NX2-2") (class "Default")
      (node (ref "N2") (pin "4") (pinfunction "2_4") (pintype "passive"))
      (node (ref "U5") (pin "13") (pinfunction "HVOUT12/53_13") (pintype "passive"))
    )
    (net (code "36") (name "/NX2-3") (class "Default")
      (node (ref "N2") (pin "5") (pinfunction "3_5") (pintype "passive"))
      (node (ref "U5") (pin "12") (pinfunction "HVOUT13/52_12") (pintype "passive"))
    )
    (net (code "37") (name "/NX2-4") (class "Default")
      (node (ref "N2") (pin "6") (pinfunction "4_6") (pintype "passive"))
      (node (ref "U5") (pin "11") (pinfunction "HVOUT14/51_11") (pintype "passive"))
    )
    (net (code "38") (name "/NX2-5") (class "Default")
      (node (ref "N2") (pin "7") (pinfunction "5_7") (pintype "passive"))
      (node (ref "U5") (pin "10") (pinfunction "HVOUT15/50_10") (pintype "passive"))
    )
    (net (code "39") (name "/NX2-6") (class "Default")
      (node (ref "N2") (pin "8") (pinfunction "6_8") (pintype "passive"))
      (node (ref "U5") (pin "9") (pinfunction "HVOUT16/49_9") (pintype "passive"))
    )
    (net (code "40") (name "/NX2-7") (class "Default")
      (node (ref "N2") (pin "9") (pinfunction "7_9") (pintype "passive"))
      (node (ref "U5") (pin "8") (pinfunction "HVOUT17/48_8") (pintype "passive"))
    )
    (net (code "41") (name "/NX2-8") (class "Default")
      (node (ref "N2") (pin "10") (pinfunction "8_10") (pintype "passive"))
      (node (ref "U5") (pin "7") (pinfunction "HVOUT18/47_7") (pintype "passive"))
    )
    (net (code "42") (name "/NX2-9") (class "Default")
      (node (ref "N2") (pin "11") (pinfunction "9_11") (pintype "passive"))
      (node (ref "U5") (pin "6") (pinfunction "HVOUT19/46_6") (pintype "passive"))
    )
    (net (code "43") (name "/NX3-0") (class "Default")
      (node (ref "N3") (pin "12") (pinfunction "0_12") (pintype "passive"))
      (node (ref "U5") (pin "75") (pinfunction "HVOUT30/35_75") (pintype "passive"))
    )
    (net (code "44") (name "/NX3-1") (class "Default")
      (node (ref "N3") (pin "3") (pinfunction "1_3") (pintype "passive"))
      (node (ref "U5") (pin "4") (pinfunction "HVOUT21/44_4") (pintype "passive"))
    )
    (net (code "45") (name "/NX3-2") (class "Default")
      (node (ref "N3") (pin "4") (pinfunction "2_4") (pintype "passive"))
      (node (ref "U5") (pin "3") (pinfunction "HVOUT22/43_3") (pintype "passive"))
    )
    (net (code "46") (name "/NX3-3") (class "Default")
      (node (ref "N3") (pin "5") (pinfunction "3_5") (pintype "passive"))
      (node (ref "U5") (pin "2") (pinfunction "HVOUT23/42_2") (pintype "passive"))
    )
    (net (code "47") (name "/NX3-4") (class "Default")
      (node (ref "N3") (pin "6") (pinfunction "4_6") (pintype "passive"))
      (node (ref "U5") (pin "1") (pinfunction "HVOUT24/41_1") (pintype "passive"))
    )
    (net (code "48") (name "/NX3-5") (class "Default")
      (node (ref "N3") (pin "7") (pinfunction "5_7") (pintype "passive"))
      (node (ref "U5") (pin "80") (pinfunction "HVOUT25/40_80") (pintype "passive"))
    )
    (net (code "49") (name "/NX3-6") (class "Default")
      (node (ref "N3") (pin "8") (pinfunction "6_8") (pintype "passive"))
      (node (ref "U5") (pin "79") (pinfunction "HVOUT26/39_79") (pintype "passive"))
    )
    (net (code "50") (name "/NX3-7") (class "Default")
      (node (ref "N3") (pin "9") (pinfunction "7_9") (pintype "passive"))
      (node (ref "U5") (pin "78") (pinfunction "HVOUT27/38_78") (pintype "passive"))
    )
    (net (code "51") (name "/NX3-8") (class "Default")
      (node (ref "N3") (pin "10") (pinfunction "8_10") (pintype "passive"))
      (node (ref "U5") (pin "77") (pinfunction "HVOUT28/37_77") (pintype "passive"))
    )
    (net (code "52") (name "/NX3-9") (class "Default")
      (node (ref "N3") (pin "11") (pinfunction "9_11") (pintype "passive"))
      (node (ref "U5") (pin "76") (pinfunction "HVOUT29/36_76") (pintype "passive"))
    )
    (net (code "53") (name "/NX4-0") (class "Default")
      (node (ref "N4") (pin "12") (pinfunction "0_12") (pintype "passive"))
      (node (ref "U5") (pin "65") (pinfunction "HVOUT40/25_65") (pintype "passive"))
    )
    (net (code "54") (name "/NX4-1") (class "Default")
      (node (ref "N4") (pin "3") (pinfunction "1_3") (pintype "passive"))
      (node (ref "U5") (pin "74") (pinfunction "HVOUT31/34_74") (pintype "passive"))
    )
    (net (code "55") (name "/NX4-2") (class "Default")
      (node (ref "N4") (pin "4") (pinfunction "2_4") (pintype "passive"))
      (node (ref "U5") (pin "73") (pinfunction "HVOUT32/33_73") (pintype "passive"))
    )
    (net (code "56") (name "/NX4-3") (class "Default")
      (node (ref "N4") (pin "5") (pinfunction "3_5") (pintype "passive"))
      (node (ref "U5") (pin "72") (pinfunction "HVOUT33/32_72") (pintype "passive"))
    )
    (net (code "57") (name "/NX4-4") (class "Default")
      (node (ref "N4") (pin "6") (pinfunction "4_6") (pintype "passive"))
      (node (ref "U5") (pin "71") (pinfunction "HVOUT34/31_71") (pintype "passive"))
    )
    (net (code "58") (name "/NX4-5") (class "Default")
      (node (ref "N4") (pin "7") (pinfunction "5_7") (pintype "passive"))
      (node (ref "U5") (pin "70") (pinfunction "HVOUT35/30_70") (pintype "passive"))
    )
    (net (code "59") (name "/NX4-6") (class "Default")
      (node (ref "N4") (pin "8") (pinfunction "6_8") (pintype "passive"))
      (node (ref "U5") (pin "69") (pinfunction "HVOUT36/29_69") (pintype "passive"))
    )
    (net (code "60") (name "/NX4-7") (class "Default")
      (node (ref "N4") (pin "9") (pinfunction "7_9") (pintype "passive"))
      (node (ref "U5") (pin "68") (pinfunction "HVOUT37/28_68") (pintype "passive"))
    )
    (net (code "61") (name "/NX4-8") (class "Default")
      (node (ref "N4") (pin "10") (pinfunction "8_10") (pintype "passive"))
      (node (ref "U5") (pin "67") (pinfunction "HVOUT38/27_67") (pintype "passive"))
    )
    (net (code "62") (name "/NX4-9") (class "Default")
      (node (ref "N4") (pin "11") (pinfunction "9_11") (pintype "passive"))
      (node (ref "U5") (pin "66") (pinfunction "HVOUT39/26_66") (pintype "passive"))
    )
    (net (code "63") (name "/NX5-0") (class "Default")
      (node (ref "N5") (pin "12") (pinfunction "0_12") (pintype "passive"))
      (node (ref "U5") (pin "55") (pinfunction "HVOUT50/15_55") (pintype "passive"))
    )
    (net (code "64") (name "/NX5-1") (class "Default")
      (node (ref "N5") (pin "3") (pinfunction "1_3") (pintype "passive"))
      (node (ref "U5") (pin "64") (pinfunction "HVOUT41/24_64") (pintype "passive"))
    )
    (net (code "65") (name "/NX5-2") (class "Default")
      (node (ref "N5") (pin "4") (pinfunction "2_4") (pintype "passive"))
      (node (ref "U5") (pin "63") (pinfunction "HVOUT42/23_63") (pintype "passive"))
    )
    (net (code "66") (name "/NX5-3") (class "Default")
      (node (ref "N5") (pin "5") (pinfunction "3_5") (pintype "passive"))
      (node (ref "U5") (pin "62") (pinfunction "HVOUT43/22_62") (pintype "passive"))
    )
    (net (code "67") (name "/NX5-4") (class "Default")
      (node (ref "N5") (pin "6") (pinfunction "4_6") (pintype "passive"))
      (node (ref "U5") (pin "61") (pinfunction "HVOUT44/21_61") (pintype "passive"))
    )
    (net (code "68") (name "/NX5-5") (class "Default")
      (node (ref "N5") (pin "7") (pinfunction "5_7") (pintype "passive"))
      (node (ref "U5") (pin "60") (pinfunction "HVOUT45/20_60") (pintype "passive"))
    )
    (net (code "69") (name "/NX5-6") (class "Default")
      (node (ref "N5") (pin "8") (pinfunction "6_8") (pintype "passive"))
      (node (ref "U5") (pin "59") (pinfunction "HVOUT46/19_59") (pintype "passive"))
    )
    (net (code "70") (name "/NX5-7") (class "Default")
      (node (ref "N5") (pin "9") (pinfunction "7_9") (pintype "passive"))
      (node (ref "U5") (pin "58") (pinfunction "HVOUT47/18_58") (pintype "passive"))
    )
    (net (code "71") (name "/NX5-8") (class "Default")
      (node (ref "N5") (pin "10") (pinfunction "8_10") (pintype "passive"))
      (node (ref "U5") (pin "57") (pinfunction "HVOUT48/17_57") (pintype "passive"))
    )
    (net (code "72") (name "/NX5-9") (class "Default")
      (node (ref "N5") (pin "11") (pinfunction "9_11") (pintype "passive"))
      (node (ref "U5") (pin "56") (pinfunction "HVOUT49/16_56") (pintype "passive"))
    )
    (net (code "73") (name "/NX6-0") (class "Default")
      (node (ref "N6") (pin "12") (pinfunction "0_12") (pintype "passive"))
      (node (ref "U5") (pin "45") (pinfunction "HVOUT60/5_45") (pintype "passive"))
    )
    (net (code "74") (name "/NX6-1") (class "Default")
      (node (ref "N6") (pin "3") (pinfunction "1_3") (pintype "passive"))
      (node (ref "U5") (pin "54") (pinfunction "HVOUT51/14_54") (pintype "passive"))
    )
    (net (code "75") (name "/NX6-2") (class "Default")
      (node (ref "N6") (pin "4") (pinfunction "2_4") (pintype "passive"))
      (node (ref "U5") (pin "53") (pinfunction "HVOUT52/13_53") (pintype "passive"))
    )
    (net (code "76") (name "/NX6-3") (class "Default")
      (node (ref "N6") (pin "5") (pinfunction "3_5") (pintype "passive"))
      (node (ref "U5") (pin "52") (pinfunction "HVOUT53/12_52") (pintype "passive"))
    )
    (net (code "77") (name "/NX6-4") (class "Default")
      (node (ref "N6") (pin "6") (pinfunction "4_6") (pintype "passive"))
      (node (ref "U5") (pin "51") (pinfunction "HVOUT54/11_51") (pintype "passive"))
    )
    (net (code "78") (name "/NX6-5") (class "Default")
      (node (ref "N6") (pin "7") (pinfunction "5_7") (pintype "passive"))
      (node (ref "U5") (pin "50") (pinfunction "HVOUT55/10_50") (pintype "passive"))
    )
    (net (code "79") (name "/NX6-6") (class "Default")
      (node (ref "N6") (pin "8") (pinfunction "6_8") (pintype "passive"))
      (node (ref "U5") (pin "49") (pinfunction "HVOUT56/9_49") (pintype "passive"))
    )
    (net (code "80") (name "/NX6-7") (class "Default")
      (node (ref "N6") (pin "9") (pinfunction "7_9") (pintype "passive"))
      (node (ref "U5") (pin "48") (pinfunction "HVOUT57/8_48") (pintype "passive"))
    )
    (net (code "81") (name "/NX6-8") (class "Default")
      (node (ref "N6") (pin "10") (pinfunction "8_10") (pintype "passive"))
      (node (ref "U5") (pin "47") (pinfunction "HVOUT58/7_47") (pintype "passive"))
    )
    (net (code "82") (name "/NX6-9") (class "Default")
      (node (ref "N6") (pin "11") (pinfunction "9_11") (pintype "passive"))
      (node (ref "U5") (pin "46") (pinfunction "HVOUT59/6_46") (pintype "passive"))
    )
    (net (code "83") (name "/OSC_IN") (class "Default")
      (node (ref "C19") (pin "2") (pinfunction "2_2") (pintype "passive"))
      (node (ref "R25") (pin "2") (pinfunction "2_2") (pintype "passive"))
      (node (ref "U2") (pin "5") (pinfunction "OSC_IN/PD0_5") (pintype "input"))
      (node (ref "Y1") (pin "2") (pinfunction "OSC2_2") (pintype "passive"))
    )
    (net (code "84") (name "/OSC_OUT") (class "Default")
      (node (ref "C20") (pin "2") (pinfunction "2_2") (pintype "passive"))
      (node (ref "R25") (pin "1") (pinfunction "1_1") (pintype "passive"))
      (node (ref "U2") (pin "6") (pinfunction "OSC_OUT/PD1_6") (pintype "output"))
      (node (ref "Y1") (pin "1") (pinfunction "OSC1_1") (pintype "passive"))
    )
    (net (code "85") (name "/RESET") (class "Default")
      (node (ref "C18") (pin "1") (pinfunction "1_1") (pintype "passive"))
      (node (ref "R20") (pin "1") (pinfunction "1_1") (pintype "passive"))
      (node (ref "RST") (pin "1") (pinfunction "1_1") (pintype "passive"))
      (node (ref "U2") (pin "7") (pinfunction "NRST_7") (pintype "bidirectional"))
    )
    (net (code "86") (name "/SCL") (class "Default")
      (node (ref "R30") (pin "1") (pinfunction "1_1") (pintype "passive"))
      (node (ref "U2") (pin "29") (pinfunction "PB10_29") (pintype "bidirectional"))
      (node (ref "U6") (pin "16") (pinfunction "SCL_16") (pintype "passive"))
      (node (ref "U7") (pin "4") (pinfunction "SCL_4") (pintype "passive"))
    )
    (net (code "87") (name "/SDA") (class "Default")
      (node (ref "R29") (pin "1") (pinfunction "1_1") (pintype "passive"))
      (node (ref "U2") (pin "30") (pinfunction "PB11_30") (pintype "bidirectional"))
      (node (ref "U6") (pin "15") (pinfunction "SDA_15") (pintype "passive"))
      (node (ref "U7") (pin "1") (pinfunction "SDA_1") (pintype "passive"))
    )
    (net (code "88") (name "/SHT_ALERT") (class "Default")
      (node (ref "U2") (pin "50") (pinfunction "PA15/JTDI_50") (pintype "bidirectional"))
      (node (ref "U7") (pin "3") (pinfunction "ALERT_3") (pintype "passive"))
    )
    (net (code "89") (name "/SWCLK") (class "Default")
      (node (ref "P1") (pin "4") (pinfunction "4_4") (pintype "passive"))
      (node (ref "U2") (pin "49") (pinfunction "PA14/JTCK/SWCLK_49") (pintype "bidirectional"))
    )
    (net (code "90") (name "/SWDIO") (class "Default")
      (node (ref "P1") (pin "3") (pinfunction "3_3") (pintype "passive"))
      (node (ref "U2") (pin "46") (pinfunction "PA13/JTMS/SWDIO_46") (pintype "bidirectional"))
    )
    (net (code "91") (name "/USB_D+") (class "Default")
      (node (ref "J2") (pin "3") (pinfunction "D+_3") (pintype "passive"))
      (node (ref "R22") (pin "1") (pinfunction "1_1") (pintype "passive"))
      (node (ref "R24") (pin "1") (pinfunction "1_1") (pintype "passive"))
    )
    (net (code "92") (name "/USB_D-") (class "Default")
      (node (ref "J2") (pin "2") (pinfunction "D-_2") (pintype "passive"))
      (node (ref "R21") (pin "1") (pinfunction "1_1") (pintype "passive"))
    )
    (net (code "93") (name "GND") (class "Default")
      (node (ref "BT") (pin "2") (pintype "passive"))
      (node (ref "C1") (pin "1") (pinfunction "1_1") (pintype "passive"))
      (node (ref "C10") (pin "2") (pinfunction "2_2") (pintype "passive"))
      (node (ref "C11") (pin "2") (pinfunction "2_2") (pintype "passive"))
      (node (ref "C12") (pin "1") (pinfunction "1_1") (pintype "passive"))
      (node (ref "C13") (pin "1") (pinfunction "1_1") (pintype "passive"))
      (node (ref "C14") (pin "1") (pinfunction "1_1") (pintype "passive"))
      (node (ref "C15") (pin "1") (pinfunction "1_1") (pintype "passive"))
      (node (ref "C16") (pin "1") (pinfunction "1_1") (pintype "passive"))
      (node (ref "C17") (pin "2") (pinfunction "2_2") (pintype "passive"))
      (node (ref "C18") (pin "2") (pinfunction "2_2") (pintype "passive"))
      (node (ref "C19") (pin "1") (pinfunction "1_1") (pintype "passive"))
      (node (ref "C2") (pin "1") (pinfunction "1_1") (pintype "passive"))
      (node (ref "C20") (pin "1") (pinfunction "1_1") (pintype "passive"))
      (node (ref "C21") (pin "1") (pinfunction "1_1") (pintype "passive"))
      (node (ref "C22") (pin "2") (pinfunction "2_2") (pintype "passive"))
      (node (ref "C23") (pin "2") (pinfunction "2_2") (pintype "passive"))
      (node (ref "C24") (pin "2") (pinfunction "2_2") (pintype "passive"))
      (node (ref "C25") (pin "2") (pinfunction "2_2") (pintype "passive"))
      (node (ref "C26") (pin "2") (pinfunction "2_2") (pintype "passive"))
      (node (ref "C27") (pin "2") (pinfunction "2_2") (pintype "passive"))
      (node (ref "C28") (pin "2") (pinfunction "2_2") (pintype "passive"))
      (node (ref "C29") (pin "2") (pinfunction "2_2") (pintype "passive"))
      (node (ref "C3") (pin "1") (pinfunction "1_1") (pintype "passive"))
      (node (ref "C4") (pin "2") (pinfunction "2_2") (pintype "passive"))
      (node (ref "C5") (pin "1") (pinfunction "1_1") (pintype "passive"))
      (node (ref "C6") (pin "1") (pinfunction "1_1") (pintype "passive"))
      (node (ref "C7") (pin "2") (pinfunction "2_2") (pintype "passive"))
      (node (ref "C8") (pin "2") (pinfunction "2_2") (pintype "passive"))
      (node (ref "C9") (pin "2") (pinfunction "2_2") (pintype "passive"))
      (node (ref "D2") (pin "1") (pinfunction "A_1") (pintype "passive"))
      (node (ref "D4") (pin "1") (pinfunction "A_1") (pintype "passive"))
      (node (ref "J1") (pin "2") (pinfunction "2_2") (pintype "power_in"))
      (node (ref "J1") (pin "3") (pinfunction "3_3") (pintype "power_in"))
      (node (ref "J2") (pin "5") (pinfunction "VSS_5") (pintype "passive"))
      (node (ref "KEY0") (pin "2") (pinfunction "2_2") (pintype "passive"))
      (node (ref "KEY1") (pin "2") (pinfunction "2_2") (pintype "passive"))
      (node (ref "KEY2") (pin "2") (pinfunction "2_2") (pintype "passive"))
      (node (ref "P1") (pin "2") (pinfunction "2_2") (pintype "passive"))
      (node (ref "Q1") (pin "3") (pinfunction "S_3") (pintype "passive"))
      (node (ref "Q2") (pin "2") (pinfunction "E_2") (pintype "passive"))
      (node (ref "Q3") (pin "2") (pinfunction "E_2") (pintype "passive"))
      (node (ref "Q4") (pin "2") (pinfunction "E_2") (pintype "passive"))
      (node (ref "Q5") (pin "2") (pinfunction "E_2") (pintype "passive"))
      (node (ref "Q6") (pin "2") (pinfunction "E_2") (pintype "passive"))
      (node (ref "R1") (pin "1") (pinfunction "1_1") (pintype "passive"))
      (node (ref "R23") (pin "1") (pinfunction "1_1") (pintype "passive"))
      (node (ref "R26") (pin "2") (pinfunction "2_2") (pintype "passive"))
      (node (ref "R3") (pin "1") (pinfunction "1_1") (pintype "passive"))
      (node (ref "RGB1") (pin "3") (pinfunction "VSS_3") (pintype "passive"))
      (node (ref "RGB2") (pin "3") (pinfunction "VSS_3") (pintype "passive"))
      (node (ref "RGB3") (pin "3") (pinfunction "VSS_3") (pintype "passive"))
      (node (ref "RGB4") (pin "3") (pinfunction "VSS_3") (pintype "passive"))
      (node (ref "RGB5") (pin "3") (pinfunction "VSS_3") (pintype "passive"))
      (node (ref "RGB6") (pin "3") (pinfunction "VSS_3") (pintype "passive"))
      (node (ref "RST") (pin "2") (pinfunction "2_2") (pintype "passive"))
      (node (ref "U1") (pin "4") (pinfunction "GND_4") (pintype "passive"))
      (node (ref "U2") (pin "12") (pinfunction "VSSA_12") (pintype "power_in"))
      (node (ref "U2") (pin "18") (pinfunction "VSS_4_18") (pintype "power_in"))
      (node (ref "U2") (pin "31") (pinfunction "VSS_1_31") (pintype "power_in"))
      (node (ref "U2") (pin "47") (pinfunction "VSS_2_47") (pintype "power_in"))
      (node (ref "U2") (pin "63") (pinfunction "VSS_3_63") (pintype "power_in"))
      (node (ref "U3") (pin "2") (pinfunction "GND_2") (pintype "power_in"))
      (node (ref "U4") (pin "1") (pinfunction "GND_1") (pintype "passive"))
      (node (ref "U5") (pin "34") (pinfunction "GND_34") (pintype "passive"))
      (node (ref "U6") (pin "10") (pinfunction "N.C._10") (pintype "passive"))
      (node (ref "U6") (pin "11") (pinfunction "N.C._11") (pintype "passive"))
      (node (ref "U6") (pin "12") (pinfunction "N.C._12") (pintype "passive"))
      (node (ref "U6") (pin "13") (pinfunction "GND_13") (pintype "passive"))
      (node (ref "U6") (pin "5") (pinfunction "N.C._5") (pintype "passive"))
      (node (ref "U6") (pin "6") (pinfunction "N.C._6") (pintype "passive"))
      (node (ref "U6") (pin "7") (pinfunction "N.C._7") (pintype "passive"))
      (node (ref "U6") (pin "8") (pinfunction "N.C._8") (pintype "passive"))
      (node (ref "U6") (pin "9") (pinfunction "N.C._9") (pintype "passive"))
      (node (ref "U7") (pin "2") (pinfunction "ADDR_2") (pintype "passive"))
      (node (ref "U7") (pin "7") (pinfunction "R_7") (pintype "passive"))
      (node (ref "U7") (pin "8") (pinfunction "VSS_8") (pintype "passive"))
      (node (ref "U7") (pin "9") (pinfunction "PAD_9") (pintype "passive"))
      (node (ref "U8") (pin "13") (pinfunction "GND_13") (pintype "passive"))
    )
    (net (code "94") (name "Net-(B-1)") (class "Default")
      (node (ref "B") (pin "2") (pinfunction "1_2") (pintype "passive"))
      (node (ref "Q6") (pin "3") (pinfunction "C_3") (pintype "passive"))
    )
    (net (code "95") (name "Net-(D1-A)") (class "Default")
      (node (ref "D1") (pin "1") (pinfunction "A_1") (pintype "passive"))
      (node (ref "L1") (pin "2") (pinfunction "2_2") (pintype "passive"))
      (node (ref "Q1") (pin "2") (pinfunction "D_2") (pintype "passive"))
    )
    (net (code "96") (name "Net-(D2-K)") (class "Default")
      (node (ref "D2") (pin "2") (pinfunction "K_2") (pintype "passive"))
      (node (ref "R31") (pin "2") (pinfunction "2_2") (pintype "passive"))
      (node (ref "U5") (pin "40") (pinfunction "VPP_40") (pintype "passive"))
    )
    (net (code "97") (name "Net-(D3-A)") (class "Default")
      (node (ref "D3") (pin "1") (pinfunction "A_1") (pintype "passive"))
      (node (ref "R32") (pin "2") (pinfunction "2_2") (pintype "passive"))
    )
    (net (code "98") (name "Net-(DS1-Pad2)") (class "Default")
      (node (ref "DS1") (pin "2") (pintype "passive"))
      (node (ref "R12") (pin "2") (pinfunction "2_2") (pintype "passive"))
    )
    (net (code "99") (name "Net-(DS2-Pad2)") (class "Default")
      (node (ref "DS2") (pin "2") (pintype "passive"))
      (node (ref "R13") (pin "2") (pinfunction "2_2") (pintype "passive"))
    )
    (net (code "100") (name "Net-(DS3-Pad2)") (class "Default")
      (node (ref "DS3") (pin "2") (pintype "passive"))
      (node (ref "R14") (pin "1") (pinfunction "1_1") (pintype "passive"))
    )
    (net (code "101") (name "Net-(DS4-Pad2)") (class "Default")
      (node (ref "DS4") (pin "2") (pintype "passive"))
      (node (ref "R15") (pin "2") (pinfunction "2_2") (pintype "passive"))
    )
    (net (code "102") (name "Net-(F1-Pad1)") (class "Default")
      (node (ref "F1") (pin "1") (pinfunction "1_1") (pintype "passive"))
      (node (ref "J1") (pin "1") (pinfunction "1_1") (pintype "power_in"))
    )
    (net (code "103") (name "Net-(J2-VCC)") (class "Default")
      (node (ref "FB1") (pin "2") (pinfunction "2_2") (pintype "passive"))
      (node (ref "J2") (pin "1") (pinfunction "VCC_1") (pintype "passive"))
    )
    (net (code "104") (name "Net-(N1-VCC)") (class "Default")
      (node (ref "N1") (pin "1") (pinfunction "VCC_1") (pintype "passive"))
      (node (ref "R6") (pin "1") (pinfunction "1_1") (pintype "passive"))
    )
    (net (code "105") (name "Net-(N2-VCC)") (class "Default")
      (node (ref "N2") (pin "1") (pinfunction "VCC_1") (pintype "passive"))
      (node (ref "R7") (pin "1") (pinfunction "1_1") (pintype "passive"))
    )
    (net (code "106") (name "Net-(N3-VCC)") (class "Default")
      (node (ref "N3") (pin "1") (pinfunction "VCC_1") (pintype "passive"))
      (node (ref "R8") (pin "1") (pinfunction "1_1") (pintype "passive"))
    )
    (net (code "107") (name "Net-(N4-VCC)") (class "Default")
      (node (ref "N4") (pin "1") (pinfunction "VCC_1") (pintype "passive"))
      (node (ref "R9") (pin "1") (pinfunction "1_1") (pintype "passive"))
    )
    (net (code "108") (name "Net-(N5-VCC)") (class "Default")
      (node (ref "N5") (pin "1") (pinfunction "VCC_1") (pintype "passive"))
      (node (ref "R10") (pin "1") (pinfunction "1_1") (pintype "passive"))
    )
    (net (code "109") (name "Net-(N6-VCC)") (class "Default")
      (node (ref "N6") (pin "1") (pinfunction "VCC_1") (pintype "passive"))
      (node (ref "R11") (pin "1") (pinfunction "1_1") (pintype "passive"))
    )
    (net (code "110") (name "Net-(Q1-G)") (class "Default")
      (node (ref "Q1") (pin "1") (pinfunction "G_1") (pintype "passive"))
      (node (ref "R1") (pin "2") (pinfunction "2_2") (pintype "passive"))
      (node (ref "U1") (pin "2") (pinfunction "SWE_2") (pintype "passive"))
    )
    (net (code "111") (name "Net-(Q2-B)") (class "Default")
      (node (ref "Q2") (pin "1") (pinfunction "B_1") (pintype "passive"))
      (node (ref "R16") (pin "2") (pinfunction "2_2") (pintype "passive"))
    )
    (net (code "112") (name "Net-(Q2-C)") (class "Default")
      (node (ref "DS1") (pin "1") (pintype "passive"))
      (node (ref "Q2") (pin "3") (pinfunction "C_3") (pintype "passive"))
    )
    (net (code "113") (name "Net-(Q3-B)") (class "Default")
      (node (ref "Q3") (pin "1") (pinfunction "B_1") (pintype "passive"))
      (node (ref "R17") (pin "2") (pinfunction "2_2") (pintype "passive"))
    )
    (net (code "114") (name "Net-(Q3-C)") (class "Default")
      (node (ref "DS2") (pin "1") (pintype "passive"))
      (node (ref "Q3") (pin "3") (pinfunction "C_3") (pintype "passive"))
    )
    (net (code "115") (name "Net-(Q4-B)") (class "Default")
      (node (ref "Q4") (pin "1") (pinfunction "B_1") (pintype "passive"))
      (node (ref "R18") (pin "2") (pinfunction "2_2") (pintype "passive"))
    )
    (net (code "116") (name "Net-(Q4-C)") (class "Default")
      (node (ref "DS3") (pin "1") (pintype "passive"))
      (node (ref "Q4") (pin "3") (pinfunction "C_3") (pintype "passive"))
    )
    (net (code "117") (name "Net-(Q5-B)") (class "Default")
      (node (ref "Q5") (pin "1") (pinfunction "B_1") (pintype "passive"))
      (node (ref "R19") (pin "2") (pinfunction "2_2") (pintype "passive"))
    )
    (net (code "118") (name "Net-(Q5-C)") (class "Default")
      (node (ref "DS4") (pin "1") (pintype "passive"))
      (node (ref "Q5") (pin "3") (pinfunction "C_3") (pintype "passive"))
    )
    (net (code "119") (name "Net-(Q6-B)") (class "Default")
      (node (ref "Q6") (pin "1") (pinfunction "B_1") (pintype "passive"))
      (node (ref "R27") (pin "2") (pinfunction "2_2") (pintype "passive"))
    )
    (net (code "120") (name "Net-(RGB1-DO)") (class "Default")
      (node (ref "RGB1") (pin "2") (pinfunction "DO_2") (pintype "passive"))
      (node (ref "RGB2") (pin "4") (pinfunction "DI_4") (pintype "passive"))
    )
    (net (code "121") (name "Net-(RGB2-DO)") (class "Default")
      (node (ref "RGB2") (pin "2") (pinfunction "DO_2") (pintype "passive"))
      (node (ref "RGB3") (pin "4") (pinfunction "DI_4") (pintype "passive"))
    )
    (net (code "122") (name "Net-(RGB3-DO)") (class "Default")
      (node (ref "RGB3") (pin "2") (pinfunction "DO_2") (pintype "passive"))
      (node (ref "RGB4") (pin "4") (pinfunction "DI_4") (pintype "passive"))
    )
    (net (code "123") (name "Net-(RGB4-DO)") (class "Default")
      (node (ref "RGB4") (pin "2") (pinfunction "DO_2") (pintype "passive"))
      (node (ref "RGB5") (pin "4") (pinfunction "DI_4") (pintype "passive"))
    )
    (net (code "124") (name "Net-(RGB5-DO)") (class "Default")
      (node (ref "RGB5") (pin "2") (pinfunction "DO_2") (pintype "passive"))
      (node (ref "RGB6") (pin "4") (pinfunction "DI_4") (pintype "passive"))
    )
    (net (code "125") (name "Net-(U1-CII)") (class "Default")
      (node (ref "C2") (pin "2") (pinfunction "2_2") (pintype "passive"))
      (node (ref "R2") (pin "2") (pinfunction "2_2") (pintype "passive"))
      (node (ref "R3") (pin "2") (pinfunction "2_2") (pintype "passive"))
      (node (ref "U1") (pin "5") (pinfunction "CII_5") (pintype "passive"))
    )
    (net (code "126") (name "Net-(U1-TC)") (class "Default")
      (node (ref "C1") (pin "2") (pinfunction "2_2") (pintype "passive"))
      (node (ref "U1") (pin "3") (pinfunction "TC_3") (pintype "passive"))
    )
    (net (code "127") (name "Net-(U2-BOOT0)") (class "Default")
      (node (ref "R23") (pin "2") (pinfunction "2_2") (pintype "passive"))
      (node (ref "U2") (pin "60") (pinfunction "BOOT0_60") (pintype "input"))
    )
    (net (code "128") (name "Net-(U2-PA11)") (class "Default")
      (node (ref "R21") (pin "2") (pinfunction "2_2") (pintype "passive"))
      (node (ref "U2") (pin "44") (pinfunction "PA11_44") (pintype "bidirectional"))
    )
    (net (code "129") (name "Net-(U2-PA12)") (class "Default")
      (node (ref "R22") (pin "2") (pinfunction "2_2") (pintype "passive"))
      (node (ref "U2") (pin "45") (pinfunction "PA12_45") (pintype "bidirectional"))
    )
    (net (code "130") (name "Net-(U2-PB2{slash}BOOT1)") (class "Default")
      (node (ref "R26") (pin "1") (pinfunction "1_1") (pintype "passive"))
      (node (ref "U2") (pin "28") (pinfunction "PB2/BOOT1_28") (pintype "bidirectional"))
    )
    (net (code "131") (name "Net-(U6-VBAT)") (class "Default")
      (node (ref "BT") (pin "1") (pintype "passive"))
      (node (ref "U6") (pin "14") (pinfunction "VBAT_14") (pintype "passive"))
    )
    (net (code "132") (name "VCC3.3") (class "Default")
      (node (ref "B") (pin "1") (pinfunction "0_1") (pintype "passive"))
      (node (ref "C10") (pin "1") (pinfunction "1_1") (pintype "passive"))
      (node (ref "C12") (pin "2") (pinfunction "2_2") (pintype "passive"))
      (node (ref "C13") (pin "2") (pinfunction "2_2") (pintype "passive"))
      (node (ref "C14") (pin "2") (pinfunction "2_2") (pintype "passive"))
      (node (ref "C15") (pin "2") (pinfunction "2_2") (pintype "passive"))
      (node (ref "C16") (pin "2") (pinfunction "2_2") (pintype "passive"))
      (node (ref "C17") (pin "1") (pinfunction "1_1") (pintype "passive"))
      (node (ref "C21") (pin "2") (pinfunction "2_2") (pintype "passive"))
      (node (ref "C23") (pin "1") (pinfunction "1_1") (pintype "passive"))
      (node (ref "C9") (pin "1") (pinfunction "1_1") (pintype "passive"))
      (node (ref "D3") (pin "2") (pinfunction "K_2") (pintype "passive"))
      (node (ref "P1") (pin "1") (pinfunction "1_1") (pintype "passive"))
      (node (ref "R20") (pin "2") (pinfunction "2_2") (pintype "passive"))
      (node (ref "R24") (pin "2") (pinfunction "2_2") (pintype "passive"))
      (node (ref "R28") (pin "2") (pinfunction "2_2") (pintype "passive"))
      (node (ref "R29") (pin "2") (pinfunction "2_2") (pintype "passive"))
      (node (ref "R30") (pin "2") (pinfunction "2_2") (pintype "passive"))
      (node (ref "U2") (pin "1") (pinfunction "VBAT_1") (pintype "power_in"))
      (node (ref "U2") (pin "13") (pinfunction "VDDA_13") (pintype "power_in"))
      (node (ref "U2") (pin "19") (pinfunction "VDD_4_19") (pintype "power_in"))
      (node (ref "U2") (pin "32") (pinfunction "VDD_1_32") (pintype "power_in"))
      (node (ref "U2") (pin "48") (pinfunction "VDD_2_48") (pintype "power_in"))
      (node (ref "U2") (pin "64") (pinfunction "VDD_3_64") (pintype "power_in"))
      (node (ref "U4") (pin "2") (pinfunction "OUT_2") (pintype "passive"))
      (node (ref "U6") (pin "2") (pinfunction "VCC_2") (pintype "passive"))
      (node (ref "U7") (pin "5") (pinfunction "VDD_5") (pintype "passive"))
      (node (ref "U7") (pin "6") (pinfunction "nRESET_6") (pintype "passive"))
      (node (ref "U8") (pin "12") (pinfunction "3.3V_12") (pintype "passive"))
    )
    (net (code "133") (name "VCC5") (class "Default")
      (node (ref "C11") (pin "1") (pinfunction "1_1") (pintype "passive"))
      (node (ref "C24") (pin "1") (pinfunction "1_1") (pintype "passive"))
      (node (ref "C25") (pin "1") (pinfunction "1_1") (pintype "passive"))
      (node (ref "C26") (pin "1") (pinfunction "1_1") (pintype "passive"))
      (node (ref "C27") (pin "1") (pinfunction "1_1") (pintype "passive"))
      (node (ref "C28") (pin "1") (pinfunction "1_1") (pintype "passive"))
      (node (ref "C29") (pin "1") (pinfunction "1_1") (pintype "passive"))
      (node (ref "C6") (pin "2") (pinfunction "2_2") (pintype "passive"))
      (node (ref "C7") (pin "1") (pinfunction "1_1") (pintype "passive"))
      (node (ref "C8") (pin "1") (pinfunction "1_1") (pintype "passive"))
      (node (ref "FB1") (pin "1") (pinfunction "1_1") (pintype "passive"))
      (node (ref "R33") (pin "2") (pinfunction "2_2") (pintype "passive"))
      (node (ref "R34") (pin "2") (pinfunction "2_2") (pintype "passive"))
      (node (ref "R35") (pin "2") (pinfunction "2_2") (pintype "passive"))
      (node (ref "R36") (pin "2") (pinfunction "2_2") (pintype "passive"))
      (node (ref "R37") (pin "2") (pinfunction "2_2") (pintype "passive"))
      (node (ref "R38") (pin "2") (pinfunction "2_2") (pintype "passive"))
      (node (ref "R39") (pin "2") (pinfunction "2_2") (pintype "passive"))
      (node (ref "RGB1") (pin "1") (pinfunction "VDD_1") (pintype "passive"))
      (node (ref "RGB2") (pin "1") (pinfunction "VDD_1") (pintype "passive"))
      (node (ref "RGB3") (pin "1") (pinfunction "VDD_1") (pintype "passive"))
      (node (ref "RGB4") (pin "1") (pinfunction "VDD_1") (pintype "passive"))
      (node (ref "RGB5") (pin "1") (pinfunction "VDD_1") (pintype "passive"))
      (node (ref "RGB6") (pin "1") (pinfunction "VDD_1") (pintype "passive"))
      (node (ref "U3") (pin "3") (pinfunction "OUT_3") (pintype "power_in"))
      (node (ref "U4") (pin "3") (pinfunction "IN_3") (pintype "passive"))
      (node (ref "U5") (pin "31") (pinfunction "~{BL}_31") (pintype "passive"))
      (node (ref "U5") (pin "32") (pinfunction "VDD_32") (pintype "passive"))
      (node (ref "U5") (pin "33") (pinfunction "DIR_33") (pintype "passive"))
    )
    (net (code "134") (name "VCC12") (class "Default")
      (node (ref "C22") (pin "1") (pinfunction "1_1") (pintype "passive"))
      (node (ref "C3") (pin "2") (pinfunction "2_2") (pintype "passive"))
      (node (ref "C5") (pin "2") (pinfunction "2_2") (pintype "passive"))
      (node (ref "D4") (pin "2") (pinfunction "K_2") (pintype "passive"))
      (node (ref "F1") (pin "2") (pinfunction "2_2") (pintype "passive"))
      (node (ref "L1") (pin "1") (pinfunction "1_1") (pintype "passive"))
      (node (ref "U1") (pin "1") (pinfunction "SWC_1") (pintype "passive"))
      (node (ref "U1") (pin "6") (pinfunction "VCC_6") (pintype "passive"))
      (node (ref "U1") (pin "7") (pinfunction "IPX_7") (pintype "passive"))
      (node (ref "U1") (pin "8") (pinfunction "DRC_8") (pintype "passive"))
      (node (ref "U3") (pin "1") (pinfunction "IN_1") (pintype "power_in"))
    )
    (net (code "135") (name "VH") (class "Default")
      (node (ref "C4") (pin "1") (pinfunction "1_1") (pintype "passive"))
      (node (ref "D1") (pin "2") (pinfunction "K_2") (pintype "passive"))
      (node (ref "R10") (pin "2") (pinfunction "2_2") (pintype "passive"))
      (node (ref "R11") (pin "2") (pinfunction "2_2") (pintype "passive"))
      (node (ref "R12") (pin "1") (pinfunction "1_1") (pintype "passive"))
      (node (ref "R13") (pin "1") (pinfunction "1_1") (pintype "passive"))
      (node (ref "R14") (pin "2") (pinfunction "2_2") (pintype "passive"))
      (node (ref "R15") (pin "1") (pinfunction "1_1") (pintype "passive"))
      (node (ref "R2") (pin "1") (pinfunction "1_1") (pintype "passive"))
      (node (ref "R31") (pin "1") (pinfunction "1_1") (pintype "passive"))
      (node (ref "R6") (pin "2") (pinfunction "2_2") (pintype "passive"))
      (node (ref "R7") (pin "2") (pinfunction "2_2") (pintype "passive"))
      (node (ref "R8") (pin "2") (pinfunction "2_2") (pintype "passive"))
      (node (ref "R9") (pin "2") (pinfunction "2_2") (pintype "passive"))
    )
    (net (code "136") (name "unconnected-(J2-ID-Pad4)") (class "Default")
      (node (ref "J2") (pin "4") (pinfunction "ID_4") (pintype "passive"))
    )
    (net (code "137") (name "unconnected-(N1-LP-Pad2)") (class "Default")
      (node (ref "N1") (pin "2") (pinfunction "LP_2") (pintype "passive"))
    )
    (net (code "138") (name "unconnected-(N1-RP-Pad13)") (class "Default")
      (node (ref "N1") (pin "13") (pinfunction "RP_13") (pintype "passive"))
    )
    (net (code "139") (name "unconnected-(N2-LP-Pad2)") (class "Default")
      (node (ref "N2") (pin "2") (pinfunction "LP_2") (pintype "passive"))
    )
    (net (code "140") (name "unconnected-(N2-RP-Pad13)") (class "Default")
      (node (ref "N2") (pin "13") (pinfunction "RP_13") (pintype "passive"))
    )
    (net (code "141") (name "unconnected-(N3-LP-Pad2)") (class "Default")
      (node (ref "N3") (pin "2") (pinfunction "LP_2") (pintype "passive"))
    )
    (net (code "142") (name "unconnected-(N3-RP-Pad13)") (class "Default")
      (node (ref "N3") (pin "13") (pinfunction "RP_13") (pintype "passive"))
    )
    (net (code "143") (name "unconnected-(N4-LP-Pad2)") (class "Default")
      (node (ref "N4") (pin "2") (pinfunction "LP_2") (pintype "passive"))
    )
    (net (code "144") (name "unconnected-(N4-RP-Pad13)") (class "Default")
      (node (ref "N4") (pin "13") (pinfunction "RP_13") (pintype "passive"))
    )
    (net (code "145") (name "unconnected-(N5-LP-Pad2)") (class "Default")
      (node (ref "N5") (pin "2") (pinfunction "LP_2") (pintype "passive"))
    )
    (net (code "146") (name "unconnected-(N5-RP-Pad13)") (class "Default")
      (node (ref "N5") (pin "13") (pinfunction "RP_13") (pintype "passive"))
    )
    (net (code "147") (name "unconnected-(N6-LP-Pad2)") (class "Default")
      (node (ref "N6") (pin "2") (pinfunction "LP_2") (pintype "passive"))
    )
    (net (code "148") (name "unconnected-(N6-RP-Pad13)") (class "Default")
      (node (ref "N6") (pin "13") (pinfunction "RP_13") (pintype "passive"))
    )
    (net (code "149") (name "unconnected-(RGB6-DO-Pad2)") (class "Default")
      (node (ref "RGB6") (pin "2") (pinfunction "DO_2") (pintype "passive"))
    )
    (net (code "150") (name "unconnected-(U2-PA0-WKUP-Pad14)") (class "Default")
      (node (ref "U2") (pin "14") (pinfunction "PA0-WKUP_14") (pintype "bidirectional"))
    )
    (net (code "151") (name "unconnected-(U2-PA1-Pad15)") (class "Default")
      (node (ref "U2") (pin "15") (pinfunction "PA1_15") (pintype "bidirectional"))
    )
    (net (code "152") (name "unconnected-(U2-PA2-Pad16)") (class "Default")
      (node (ref "U2") (pin "16") (pinfunction "PA2_16") (pintype "bidirectional"))
    )
    (net (code "153") (name "unconnected-(U2-PA3-Pad17)") (class "Default")
      (node (ref "U2") (pin "17") (pinfunction "PA3_17") (pintype "bidirectional"))
    )
    (net (code "154") (name "unconnected-(U2-PA8-Pad41)") (class "Default")
      (node (ref "U2") (pin "41") (pinfunction "PA8_41") (pintype "bidirectional"))
    )
    (net (code "155") (name "unconnected-(U2-PB0-Pad26)") (class "Default")
      (node (ref "U2") (pin "26") (pinfunction "PB0_26") (pintype "bidirectional"))
    )
    (net (code "156") (name "unconnected-(U2-PB1-Pad27)") (class "Default")
      (node (ref "U2") (pin "27") (pinfunction "PB1_27") (pintype "bidirectional"))
    )
    (net (code "157") (name "unconnected-(U2-PB3{slash}JTDO-Pad55)") (class "Default")
      (node (ref "U2") (pin "55") (pinfunction "PB3/JTDO_55") (pintype "bidirectional"))
    )
    (net (code "158") (name "unconnected-(U2-PB6-Pad58)") (class "Default")
      (node (ref "U2") (pin "58") (pinfunction "PB6_58") (pintype "bidirectional"))
    )
    (net (code "159") (name "unconnected-(U2-PB7-Pad59)") (class "Default")
      (node (ref "U2") (pin "59") (pinfunction "PB7_59") (pintype "bidirectional"))
    )
    (net (code "160") (name "unconnected-(U2-PB8-Pad61)") (class "Default")
      (node (ref "U2") (pin "61") (pinfunction "PB8_61") (pintype "bidirectional"))
    )
    (net (code "161") (name "unconnected-(U2-PB9-Pad62)") (class "Default")
      (node (ref "U2") (pin "62") (pinfunction "PB9_62") (pintype "bidirectional"))
    )
    (net (code "162") (name "unconnected-(U2-PC4-Pad24)") (class "Default")
      (node (ref "U2") (pin "24") (pinfunction "PC4_24") (pintype "bidirectional"))
    )
    (net (code "163") (name "unconnected-(U2-PC5-Pad25)") (class "Default")
      (node (ref "U2") (pin "25") (pinfunction "PC5_25") (pintype "bidirectional"))
    )
    (net (code "164") (name "unconnected-(U2-PC7-Pad38)") (class "Default")
      (node (ref "U2") (pin "38") (pinfunction "PC7_38") (pintype "bidirectional"))
    )
    (net (code "165") (name "unconnected-(U2-PC8-Pad39)") (class "Default")
      (node (ref "U2") (pin "39") (pinfunction "PC8_39") (pintype "bidirectional"))
    )
    (net (code "166") (name "unconnected-(U2-PC14-OSC32_IN-Pad3)") (class "Default")
      (node (ref "U2") (pin "3") (pinfunction "PC14-OSC32_IN_3") (pintype "bidirectional"))
    )
    (net (code "167") (name "unconnected-(U2-PC15-OSC32_OUT-Pad4)") (class "Default")
      (node (ref "U2") (pin "4") (pinfunction "PC15-OSC32_OUT_4") (pintype "bidirectional"))
    )
    (net (code "168") (name "unconnected-(U2-PD2-Pad54)") (class "Default")
      (node (ref "U2") (pin "54") (pinfunction "PD2_54") (pintype "bidirectional"))
    )
    (net (code "169") (name "unconnected-(U5-DOUT1{slash}DIN4(B)-Pad39)") (class "Default")
      (node (ref "U5") (pin "39") (pinfunction "DOUT1/DIN4(B)_39") (pintype "passive"))
    )
    (net (code "170") (name "unconnected-(U5-DOUT2{slash}DIN3(B)-Pad38)") (class "Default")
      (node (ref "U5") (pin "38") (pinfunction "DOUT2/DIN3(B)_38") (pintype "passive"))
    )
    (net (code "171") (name "unconnected-(U5-DOUT3{slash}DIN2(B)-Pad37)") (class "Default")
      (node (ref "U5") (pin "37") (pinfunction "DOUT3/DIN2(B)_37") (pintype "passive"))
    )
    (net (code "172") (name "unconnected-(U5-DOUT4{slash}DIN1(B)-Pad36)") (class "Default")
      (node (ref "U5") (pin "36") (pinfunction "DOUT4/DIN1(B)_36") (pintype "passive"))
    )
    (net (code "173") (name "unconnected-(U5-HVOUT61{slash}4-Pad44)") (class "Default")
      (node (ref "U5") (pin "44") (pinfunction "HVOUT61/4_44") (pintype "passive"))
    )
    (net (code "174") (name "unconnected-(U5-HVOUT62{slash}3-Pad43)") (class "Default")
      (node (ref "U5") (pin "43") (pinfunction "HVOUT62/3_43") (pintype "passive"))
    )
    (net (code "175") (name "unconnected-(U5-HVOUT63{slash}2-Pad42)") (class "Default")
      (node (ref "U5") (pin "42") (pinfunction "HVOUT63/2_42") (pintype "passive"))
    )
    (net (code "176") (name "unconnected-(U5-HVOUT64{slash}1-Pad41)") (class "Default")
      (node (ref "U5") (pin "41") (pinfunction "HVOUT64/1_41") (pintype "passive"))
    )
    (net (code "177") (name "unconnected-(U6-32kHz-Pad1)") (class "Default")
      (node (ref "U6") (pin "1") (pinfunction "32kHz_1") (pintype "passive"))
    )
    (net (code "178") (name "unconnected-(U6-~{RST}-Pad4)") (class "Default")
      (node (ref "U6") (pin "4") (pinfunction "~{RST}_4") (pintype "passive"))
    )
    (net (code "179") (name "unconnected-(U8-KEY--Pad15)") (class "Default")
      (node (ref "U8") (pin "15") (pinfunction "KEY-_15") (pintype "passive"))
    )
    (net (code "180") (name "unconnected-(U8-LED-Pad16)") (class "Default")
      (node (ref "U8") (pin "16") (pinfunction "LED_16") (pintype "passive"))
    )
    (net (code "181") (name "unconnected-(U8-LEDCON-Pad14)") (class "Default")
      (node (ref "U8") (pin "14") (pinfunction "LEDCON_14") (pintype "passive"))
    )
    (net (code "182") (name "unconnected-(U8-NC-Pad3)") (class "Default")
      (node (ref "U8") (pin "3") (pinfunction "NC_3") (pintype "passive"))
    )
    (net (code "183") (name "unconnected-(U8-NC-Pad4)") (class "Default")
      (node (ref "U8") (pin "4") (pinfunction "NC_4") (pintype "passive"))
    )
    (net (code "184") (name "unconnected-(U8-NC-Pad5)") (class "Default")
      (node (ref "U8") (pin "5") (pinfunction "NC_5") (pintype "passive"))
    )
    (net (code "185") (name "unconnected-(U8-NC-Pad6)") (class "Default")
      (node (ref "U8") (pin "6") (pinfunction "NC_6") (pintype "passive"))
    )
    (net (code "186") (name "unconnected-(U8-NC-Pad7)") (class "Default")
      (node (ref "U8") (pin "7") (pinfunction "NC_7") (pintype "passive"))
    )
    (net (code "187") (name "unconnected-(U8-NC-Pad8)") (class "Default")
      (node (ref "U8") (pin "8") (pinfunction "NC_8") (pintype "passive"))
    )
    (net (code "188") (name "unconnected-(U8-NC-Pad9)") (class "Default")
      (node (ref "U8") (pin "9") (pinfunction "NC_9") (pintype "passive"))
    )
    (net (code "189") (name "unconnected-(U8-NC-Pad10)") (class "Default")
      (node (ref "U8") (pin "10") (pinfunction "NC_10") (pintype "passive"))
    )
    (net (code "190") (name "unconnected-(U8-NC-Pad19)") (class "Default")
      (node (ref "U8") (pin "19") (pinfunction "NC_19") (pintype "passive"))
    )
    (net (code "191") (name "unconnected-(U8-NC-Pad20)") (class "Default")
      (node (ref "U8") (pin "20") (pinfunction "NC_20") (pintype "passive"))
    )
    (net (code "192") (name "unconnected-(U8-NC-Pad21)") (class "Default")
      (node (ref "U8") (pin "21") (pinfunction "NC_21") (pintype "passive"))
    )
    (net (code "193") (name "unconnected-(U8-NC-Pad22)") (class "Default")
      (node (ref "U8") (pin "22") (pinfunction "NC_22") (pintype "passive"))
    )
    (net (code "194") (name "unconnected-(U8-NC-Pad23)") (class "Default")
      (node (ref "U8") (pin "23") (pinfunction "NC_23") (pintype "passive"))
    )
    (net (code "195") (name "unconnected-(U8-NC-Pad24)") (class "Default")
      (node (ref "U8") (pin "24") (pinfunction "NC_24") (pintype "passive"))
    )
    (net (code "196") (name "unconnected-(U8-NC-Pad25)") (class "Default")
      (node (ref "U8") (pin "25") (pinfunction "NC_25") (pintype "passive"))
    )
    (net (code "197") (name "unconnected-(U8-NC-Pad26)") (class "Default")
      (node (ref "U8") (pin "26") (pinfunction "NC_26") (pintype "passive"))
    )
    (net (code "198") (name "unconnected-(U8-~{RST}-Pad11)") (class "Default")
      (node (ref "U8") (pin "11") (pinfunction "~{RST}_11") (pintype "passive"))
    )
  )
)
